# Main.net
KiCad netlist of a schematic drawn in Altium Designer
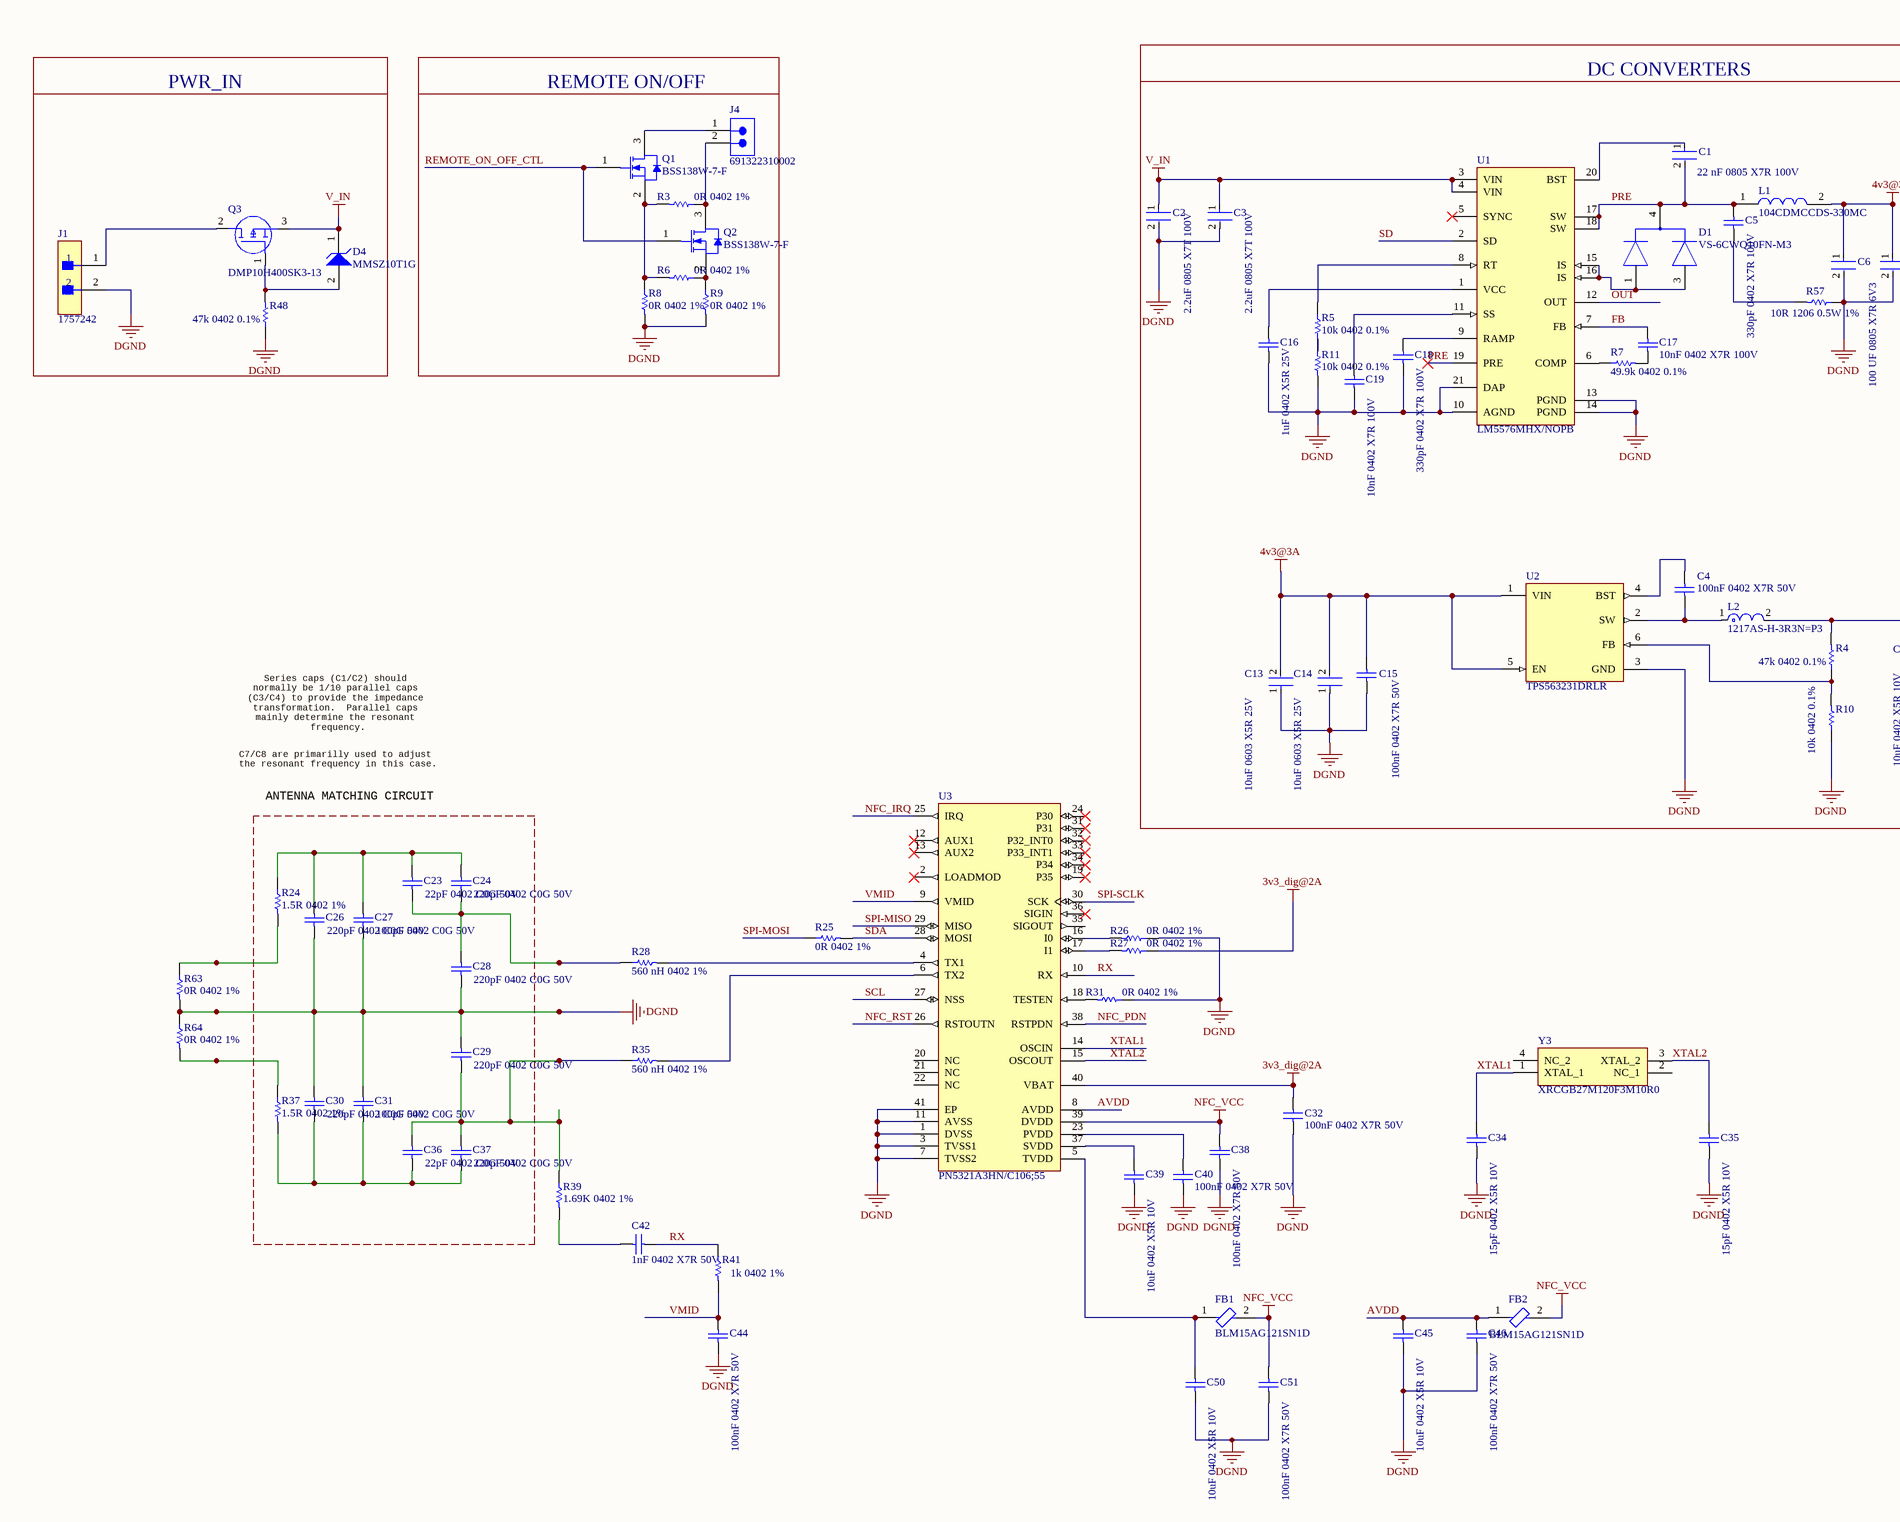
[diagram p0: Main.SchDoc, top left]
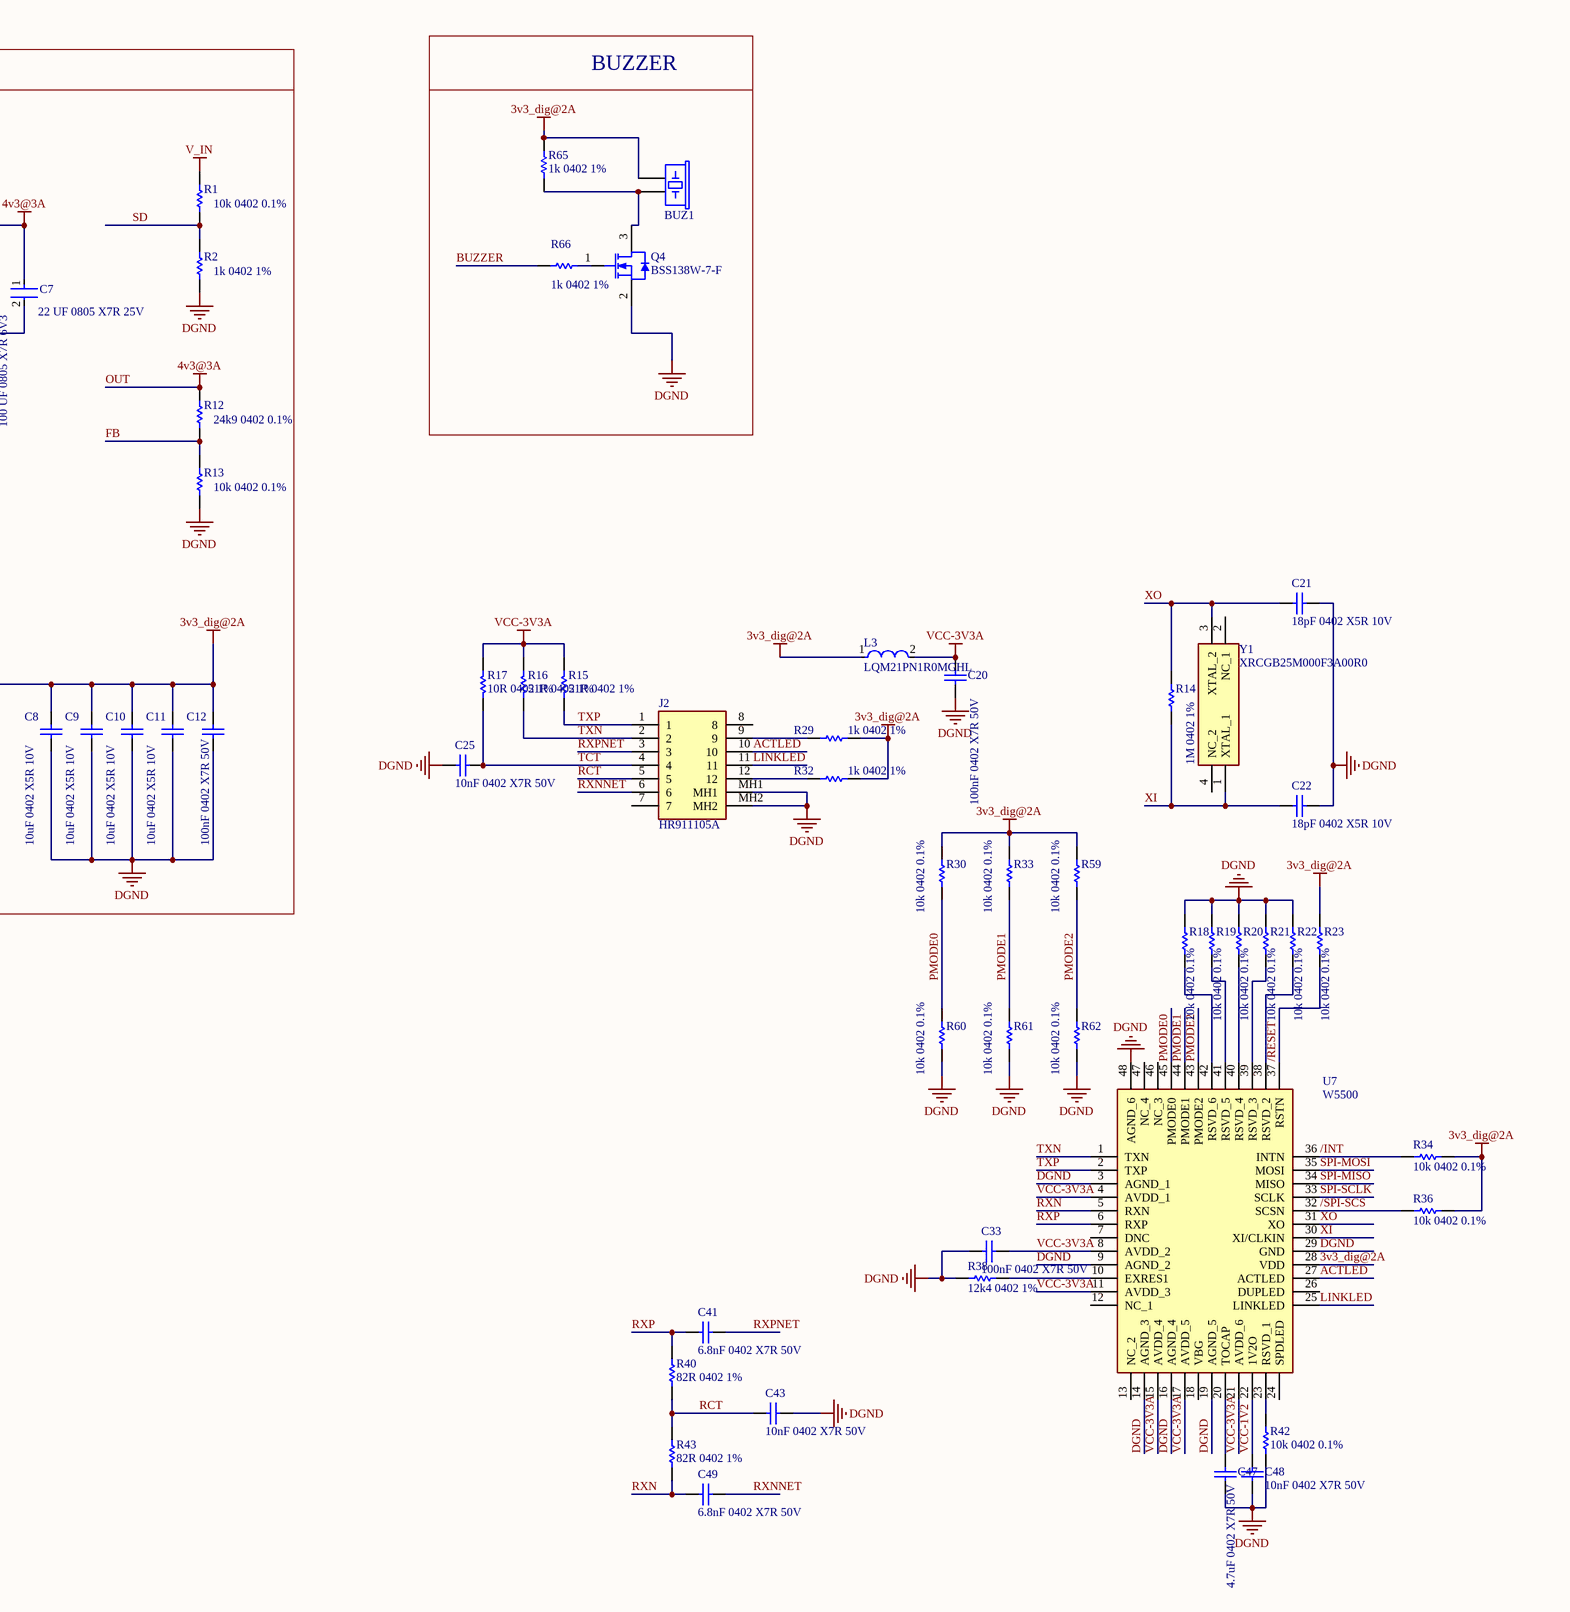
[diagram p1: Main.SchDoc, top right]
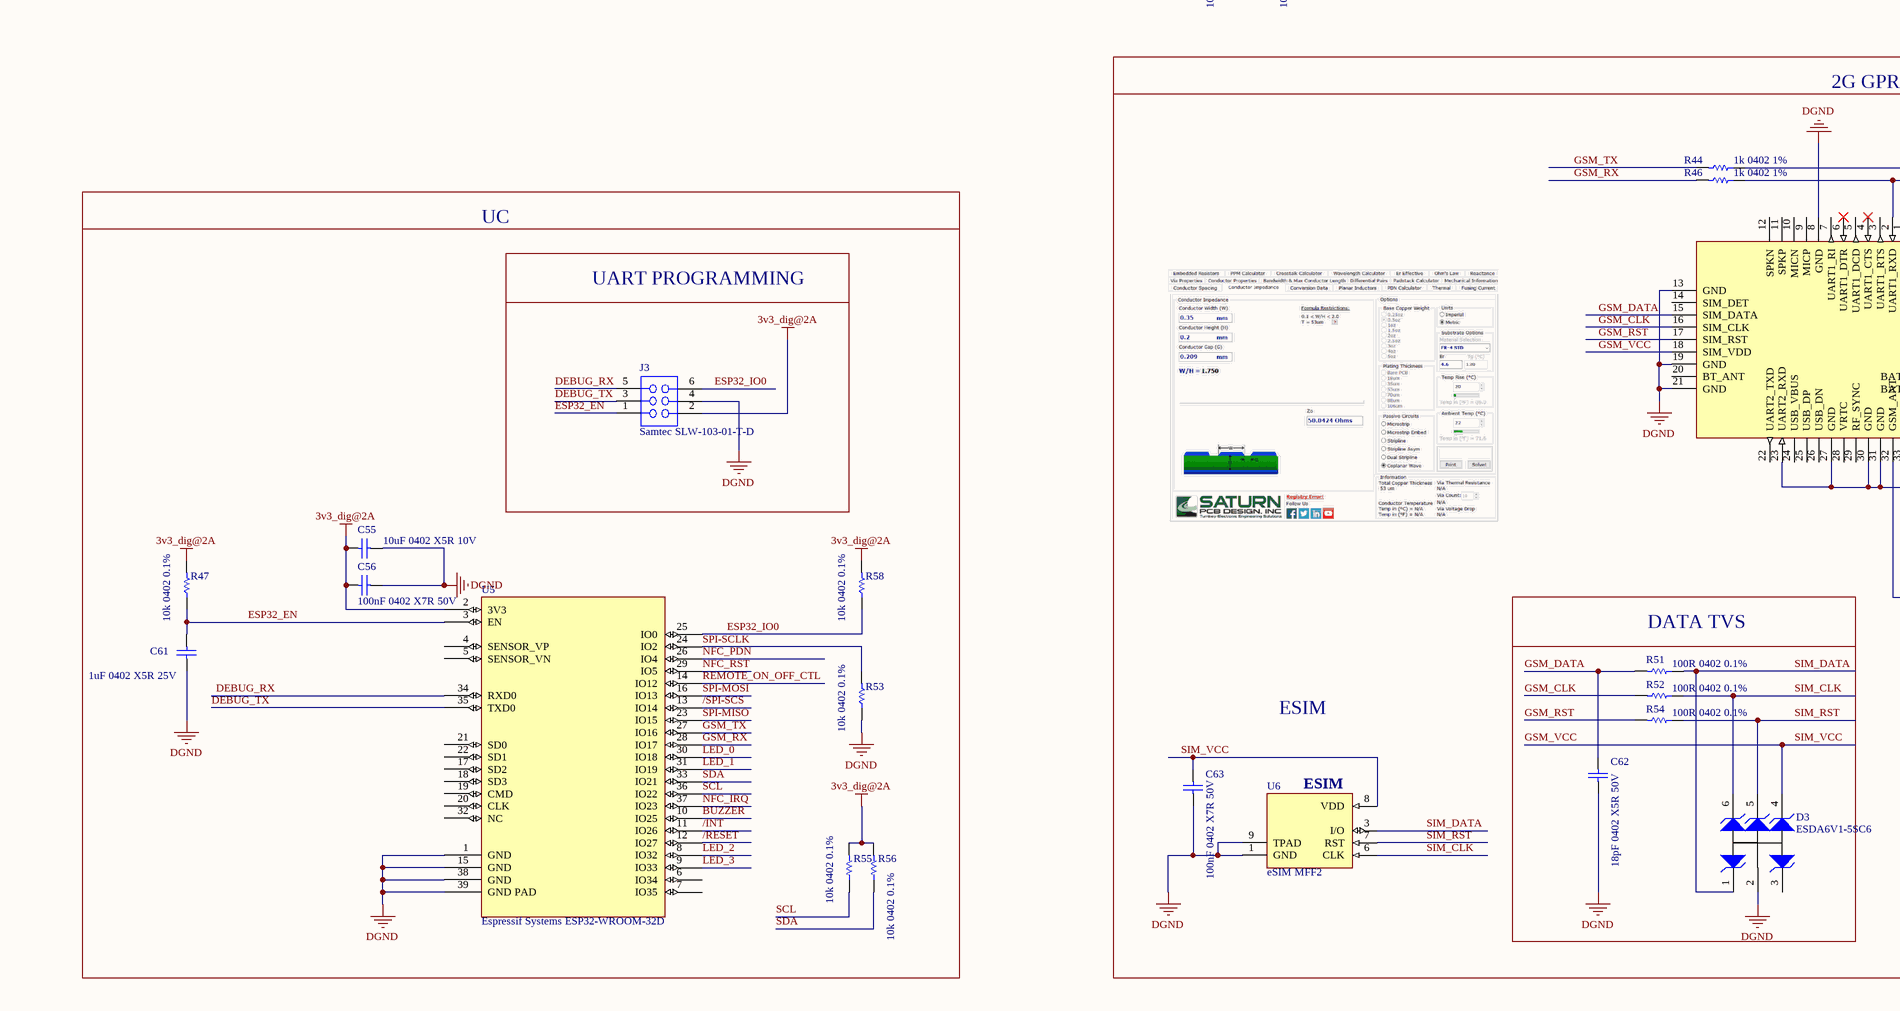
[diagram p2: Main.SchDoc, bottom left]
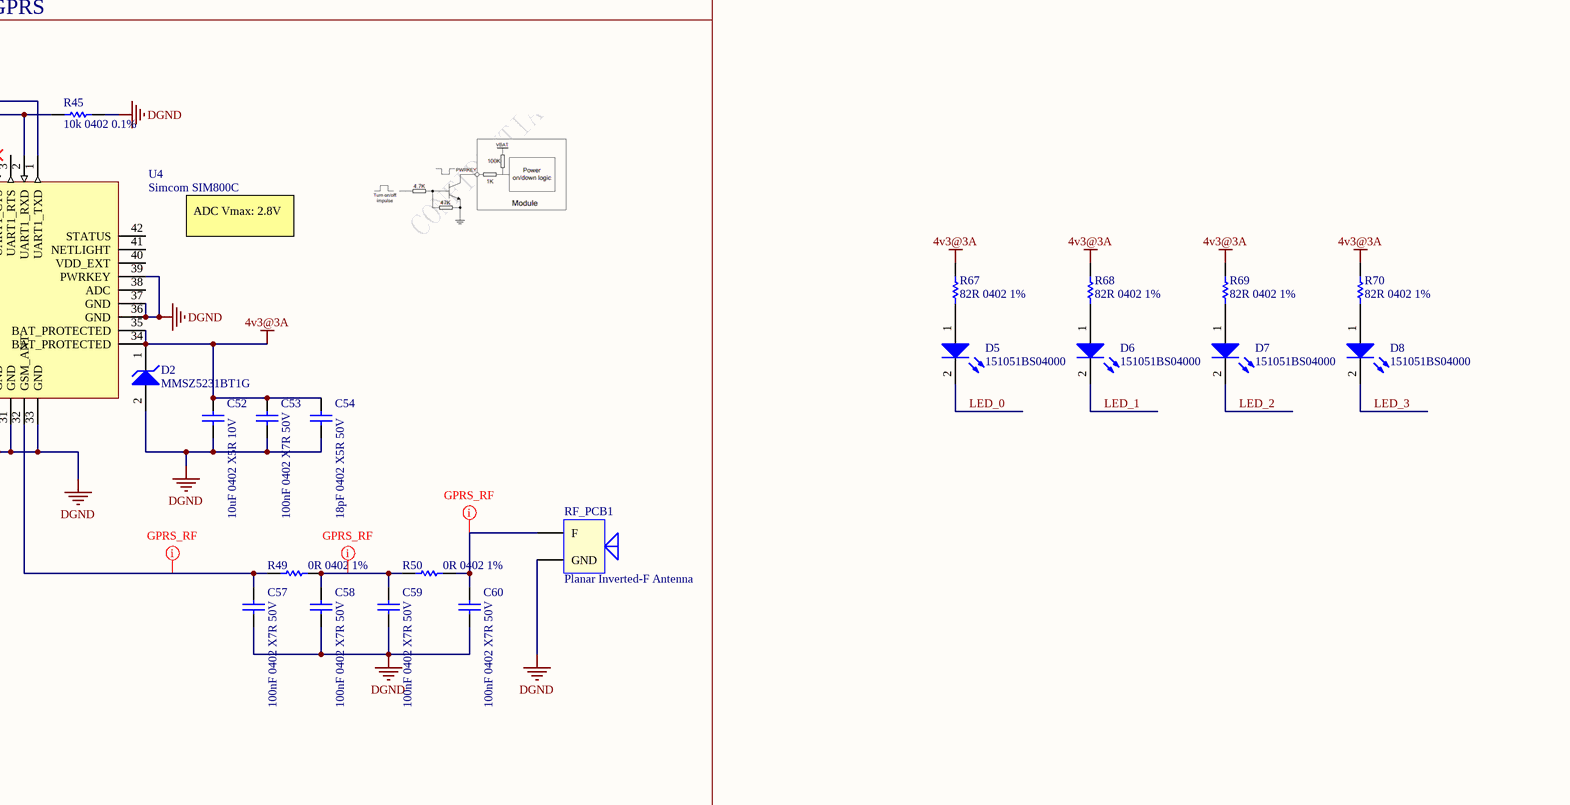
[diagram p3: Main.SchDoc, bottom right]

(export (version "E")
  (design (tool "Eeschema 10.0.6"))
  (components
    (comp (ref "BUZ1")
      (value "CUI CMT-1285C-035")
      (footprint "BUZZER-12MM-NS")
      (description "Audio Buzzer Magnetic 3Vo-p 5Vo-p 70mA 3.5Vo-p 85dB Through Hole Pin Tray")
      (fields (field (name "MANUFACTURER PART NUMBER") "CMT-1285C-035"))
      (libsource (lib "in3ator") (part "CMP-581a9557be5887dd-1"))
    )
    (comp (ref "C1")
      (value "22 nF 0805 X7R 100V")
      (footprint "FP-GRM21B-0_15-IPC_C")
      (fields (field (name "VOLTAGE") "25V") (field (name "TOLERANCE") "10%"))
      (libsource (lib "Altium Content Vault") (part "b4654b650e69147ec39a6b967a45e02"))
    )
    (comp (ref "C2")
      (value "2.2uF 0805 X7T 100V")
      (footprint "FP-GRM21B-0_15-IPC_C")
      (description "Chip Multilayer Ceramic Capacitors for General Purpose, 0805, 2.2uF, X7T, 15%, 10%, 100V")
      (fields (field (name "VOLTAGE") "25V") (field (name "TOLERANCE") "10%"))
      (libsource (lib "Altium Content Vault") (part "b4654b650e69147ec39a6b967a45e02"))
    )
    (comp (ref "C3")
      (value "2.2uF 0805 X7T 100V")
      (footprint "FP-GRM21B-0_15-IPC_C")
      (description "Chip Multilayer Ceramic Capacitors for General Purpose, 0805, 2.2uF, X7T, 15%, 10%, 100V")
      (fields (field (name "VOLTAGE") "25V") (field (name "TOLERANCE") "10%"))
      (libsource (lib "Altium Content Vault") (part "b4654b650e69147ec39a6b967a45e02"))
    )
    (comp (ref "C4")
      (value "100nF 0402 X7R 50V")
      (footprint "CAPC1005X55X25NL5T10")
      (libsource (lib "Altium Content Vault") (part "CAP-NP-2"))
    )
    (comp (ref "C5")
      (value "330pF 0402 X7R 100V")
      (footprint "CAPC1005X55X25NL5T10")
      (libsource (lib "Altium Content Vault") (part "CAP-NP-2"))
    )
    (comp (ref "C6")
      (value "100 UF 0805 X7R 6V3")
      (footprint "FP-GRM21B-0_15-IPC_C")
      (fields (field (name "VOLTAGE") "25V") (field (name "TOLERANCE") "10%"))
      (libsource (lib "Altium Content Vault") (part "b4654b650e69147ec39a6b967a45e02"))
    )
    (comp (ref "C7")
      (value "22 UF 0805 X7R 25V")
      (footprint "FP-GRM21B-0_15-IPC_C")
      (fields (field (name "VOLTAGE") "25V") (field (name "TOLERANCE") "10%"))
      (libsource (lib "Altium Content Vault") (part "b4654b650e69147ec39a6b967a45e02"))
    )
    (comp (ref "C8")
      (value "10uF 0402 X5R 10V")
      (footprint "CAPC1005X55X25NL5T10")
      (libsource (lib "Altium Content Vault") (part "CAP-NP-2"))
    )
    (comp (ref "C9")
      (value "10uF 0402 X5R 10V")
      (footprint "CAPC1005X55X25NL5T10")
      (libsource (lib "Altium Content Vault") (part "CAP-NP-2"))
    )
    (comp (ref "C10")
      (value "10uF 0402 X5R 10V")
      (footprint "CAPC1005X55X25NL5T10")
      (libsource (lib "Altium Content Vault") (part "CAP-NP-2"))
    )
    (comp (ref "C11")
      (value "10uF 0402 X5R 10V")
      (footprint "CAPC1005X55X25NL5T10")
      (libsource (lib "Altium Content Vault") (part "CAP-NP-2"))
    )
    (comp (ref "C12")
      (value "100nF 0402 X7R 50V")
      (footprint "CAPC1005X55X25NL5T10")
      (libsource (lib "Altium Content Vault") (part "CAP-NP-2"))
    )
    (comp (ref "C13")
      (value "10uF 0603 X5R 25V")
      (footprint "FP-GRM188-0_2-IPC_B")
      (libsource (lib "Altium Content Vault") (part "11868f565c42a9108669ba33697ecf6"))
    )
    (comp (ref "C14")
      (value "10uF 0603 X5R 25V")
      (footprint "FP-GRM188-0_2-IPC_B")
      (libsource (lib "Altium Content Vault") (part "11868f565c42a9108669ba33697ecf6"))
    )
    (comp (ref "C15")
      (value "100nF 0402 X7R 50V")
      (footprint "CAPC1005X55X25NL5T10")
      (libsource (lib "Altium Content Vault") (part "CAP-NP-2"))
    )
    (comp (ref "C16")
      (value "1uF 0402 X5R 25V")
      (footprint "CAPC1005X55X25NL5T10")
      (libsource (lib "Altium Content Vault") (part "CAP-NP-2"))
    )
    (comp (ref "C17")
      (value "10nF 0402 X7R 100V")
      (footprint "CAPC1005X55X25NL5T10")
      (libsource (lib "Altium Content Vault") (part "CAP-NP-2"))
    )
    (comp (ref "C18")
      (value "330pF 0402 X7R 100V")
      (footprint "CAPC1005X55X25NL5T10")
      (libsource (lib "Altium Content Vault") (part "CAP-NP-2"))
    )
    (comp (ref "C19")
      (value "10nF 0402 X7R 100V")
      (footprint "CAPC1005X55X25NL5T10")
      (libsource (lib "Altium Content Vault") (part "CAP-NP-2"))
    )
    (comp (ref "C20")
      (value "100nF 0402 X7R 50V")
      (footprint "CAPC1005X55X25NL5T10")
      (libsource (lib "Altium Content Vault") (part "CAP-NP-2"))
    )
    (comp (ref "C21")
      (value "18pF 0402 X5R 10V")
      (footprint "CAPC1005X55X25NL5T10")
      (libsource (lib "Altium Content Vault") (part "CAP-NP-2"))
    )
    (comp (ref "C22")
      (value "18pF 0402 X5R 10V")
      (footprint "CAPC1005X55X25NL5T10")
      (libsource (lib "Altium Content Vault") (part "CAP-NP-2"))
    )
    (comp (ref "C23")
      (value "22pF 0402 C0G 50V")
      (footprint "CAPC1005X55X25NL5T10")
      (libsource (lib "Altium Content Vault") (part "CAP-NP-2"))
    )
    (comp (ref "C24")
      (value "220pF 0402 C0G 50V")
      (footprint "CAPC1005X55X25NL5T10")
      (libsource (lib "Altium Content Vault") (part "CAP-NP-2"))
    )
    (comp (ref "C25")
      (value "10nF 0402 X7R 50V")
      (footprint "CAPC1005X55X25NL5T10")
      (libsource (lib "Altium Content Vault") (part "CAP-NP-2"))
    )
    (comp (ref "C26")
      (value "220pF 0402 C0G 50V")
      (footprint "CAPC1005X55X25NL5T10")
      (libsource (lib "Altium Content Vault") (part "CAP-NP-2"))
    )
    (comp (ref "C27")
      (value "100pF 0402 C0G 50V")
      (footprint "CAPC1005X55X25NL5T10")
      (libsource (lib "Altium Content Vault") (part "CAP-NP-2"))
    )
    (comp (ref "C28")
      (value "220pF 0402 C0G 50V")
      (footprint "CAPC1005X55X25NL5T10")
      (libsource (lib "Altium Content Vault") (part "CAP-NP-2"))
    )
    (comp (ref "C29")
      (value "220pF 0402 C0G 50V")
      (footprint "CAPC1005X55X25NL5T10")
      (libsource (lib "Altium Content Vault") (part "CAP-NP-2"))
    )
    (comp (ref "C30")
      (value "220pF 0402 C0G 50V")
      (footprint "CAPC1005X55X25NL5T10")
      (libsource (lib "Altium Content Vault") (part "CAP-NP-2"))
    )
    (comp (ref "C31")
      (value "100pF 0402 C0G 50V")
      (footprint "CAPC1005X55X25NL5T10")
      (libsource (lib "Altium Content Vault") (part "CAP-NP-2"))
    )
    (comp (ref "C32")
      (value "100nF 0402 X7R 50V")
      (footprint "CAPC1005X55X25NL5T10")
      (libsource (lib "Altium Content Vault") (part "CAP-NP-2"))
    )
    (comp (ref "C33")
      (value "100nF 0402 X7R 50V")
      (footprint "CAPC1005X55X25NL5T10")
      (libsource (lib "Altium Content Vault") (part "CAP-NP-2"))
    )
    (comp (ref "C34")
      (value "15pF 0402 X5R 10V")
      (footprint "CAPC1005X55X25NL5T10")
      (libsource (lib "Altium Content Vault") (part "CAP-NP-2"))
    )
    (comp (ref "C35")
      (value "15pF 0402 X5R 10V")
      (footprint "CAPC1005X55X25NL5T10")
      (libsource (lib "Altium Content Vault") (part "CAP-NP-2"))
    )
    (comp (ref "C36")
      (value "22pF 0402 C0G 50V")
      (footprint "CAPC1005X55X25NL5T10")
      (libsource (lib "Altium Content Vault") (part "CAP-NP-2"))
    )
    (comp (ref "C37")
      (value "220pF 0402 C0G 50V")
      (footprint "CAPC1005X55X25NL5T10")
      (libsource (lib "Altium Content Vault") (part "CAP-NP-2"))
    )
    (comp (ref "C38")
      (value "100nF 0402 X7R 50V")
      (footprint "CAPC1005X55X25NL5T10")
      (libsource (lib "Altium Content Vault") (part "CAP-NP-2"))
    )
    (comp (ref "C39")
      (value "10uF 0402 X5R 10V")
      (footprint "CAPC1005X55X25NL5T10")
      (libsource (lib "Altium Content Vault") (part "CAP-NP-2"))
    )
    (comp (ref "C40")
      (value "100nF 0402 X7R 50V")
      (footprint "CAPC1005X55X25NL5T10")
      (libsource (lib "Altium Content Vault") (part "CAP-NP-2"))
    )
    (comp (ref "C41")
      (value "6.8nF 0402 X7R 50V")
      (footprint "CAPC1005X55X25NL5T10")
      (libsource (lib "Altium Content Vault") (part "CAP-NP-2"))
    )
    (comp (ref "C42")
      (value "1nF 0402 X7R 50V")
      (footprint "CAPC1005X55X25NL5T10")
      (libsource (lib "Altium Content Vault") (part "CAP-NP-2"))
    )
    (comp (ref "C43")
      (value "10nF 0402 X7R 50V")
      (footprint "CAPC1005X55X25NL5T10")
      (libsource (lib "Altium Content Vault") (part "CAP-NP-2"))
    )
    (comp (ref "C44")
      (value "100nF 0402 X7R 50V")
      (footprint "CAPC1005X55X25NL5T10")
      (libsource (lib "Altium Content Vault") (part "CAP-NP-2"))
    )
    (comp (ref "C45")
      (value "10uF 0402 X5R 10V")
      (footprint "CAPC1005X55X25NL5T10")
      (libsource (lib "Altium Content Vault") (part "CAP-NP-2"))
    )
    (comp (ref "C46")
      (value "100nF 0402 X7R 50V")
      (footprint "CAPC1005X55X25NL5T10")
      (libsource (lib "Altium Content Vault") (part "CAP-NP-2"))
    )
    (comp (ref "C47")
      (value "4.7uF 0402 X7R 50V")
      (footprint "CAPC1005X55X25NL5T10")
      (libsource (lib "Altium Content Vault") (part "CAP-NP-2"))
    )
    (comp (ref "C48")
      (value "10nF 0402 X7R 50V")
      (footprint "CAPC1005X55X25NL5T10")
      (libsource (lib "Altium Content Vault") (part "CAP-NP-2"))
    )
    (comp (ref "C49")
      (value "6.8nF 0402 X7R 50V")
      (footprint "CAPC1005X55X25NL5T10")
      (libsource (lib "Altium Content Vault") (part "CAP-NP-2"))
    )
    (comp (ref "C50")
      (value "10uF 0402 X5R 10V")
      (footprint "CAPC1005X55X25NL5T10")
      (libsource (lib "Altium Content Vault") (part "CAP-NP-2"))
    )
    (comp (ref "C51")
      (value "100nF 0402 X7R 50V")
      (footprint "CAPC1005X55X25NL5T10")
      (libsource (lib "Altium Content Vault") (part "CAP-NP-2"))
    )
    (comp (ref "C52")
      (value "10uF 0402 X5R 10V")
      (footprint "CAPC1005X55X25NL5T10")
      (libsource (lib "Altium Content Vault") (part "CAP-NP-2"))
    )
    (comp (ref "C53")
      (value "100nF 0402 X7R 50V")
      (footprint "CAPC1005X55X25NL5T10")
      (libsource (lib "Altium Content Vault") (part "CAP-NP-2"))
    )
    (comp (ref "C54")
      (value "18pF 0402 X5R 50V")
      (footprint "CAPC1005X55X25NL5T10")
      (libsource (lib "Altium Content Vault") (part "CAP-NP-2"))
    )
    (comp (ref "C55")
      (value "10uF 0402 X5R 10V")
      (footprint "CAPC1005X55X25NL5T10")
      (libsource (lib "Altium Content Vault") (part "CAP-NP-2"))
    )
    (comp (ref "C56")
      (value "100nF 0402 X7R 50V")
      (footprint "CAPC1005X55X25NL5T10")
      (libsource (lib "Altium Content Vault") (part "CAP-NP-2"))
    )
    (comp (ref "C57")
      (value "100nF 0402 X7R 50V")
      (footprint "CAPC1005X55X25NL5T10")
      (libsource (lib "Altium Content Vault") (part "CAP-NP-2"))
    )
    (comp (ref "C58")
      (value "100nF 0402 X7R 50V")
      (footprint "CAPC1005X55X25NL5T10")
      (libsource (lib "Altium Content Vault") (part "CAP-NP-2"))
    )
    (comp (ref "C59")
      (value "100nF 0402 X7R 50V")
      (footprint "CAPC1005X55X25NL5T10")
      (libsource (lib "Altium Content Vault") (part "CAP-NP-2"))
    )
    (comp (ref "C60")
      (value "100nF 0402 X7R 50V")
      (footprint "CAPC1005X55X25NL5T10")
      (libsource (lib "Altium Content Vault") (part "CAP-NP-2"))
    )
    (comp (ref "C61")
      (value "1uF 0402 X5R 25V")
      (footprint "CAPC1005X55X25NL5T10")
      (libsource (lib "Altium Content Vault") (part "CAP-NP-2"))
    )
    (comp (ref "C62")
      (value "18pF 0402 X5R 50V")
      (footprint "CAPC1005X55X25NL5T10")
      (libsource (lib "Altium Content Vault") (part "CAP-NP-2"))
    )
    (comp (ref "C63")
      (value "100nF 0402 X7R 50V")
      (footprint "CAPC1005X55X25NL5T10")
      (libsource (lib "Altium Content Vault") (part "CAP-NP-2"))
    )
    (comp (ref "D1")
      (value "VS-6CWQ10FN-M3")
      (footprint "FP-95627-0")
      (description "VS-6CWQ10FN-M3 Rectifier Diode, Schottky, 1 Phase, 2 Element, 7A, 100V V(RRM), Silicon, TO-252AA")
      (libsource (lib "Altium Content Vault") (part "8cea5ace56f6096956c40e30c0f019d"))
    )
    (comp (ref "D2")
      (value "MMSZ5231BT1G")
      (footprint "ONSC-SOD-123-2-425-04_V")
      (description "Zener Voltage Regulator, 500 mW, 2-Pin SOD-123, Pb-Free, Tape and Reel")
      (fields (field (name "MANUFACTURER") "On Semiconductor"))
      (libsource (lib "Altium Content Vault") (part "ONSC-K1A2-2"))
    )
    (comp (ref "D3")
      (value "ESDA6V1-5SC6")
      (footprint "MF06A_N")
      (description "ESDA Series 5 Channel 6.1 V 50 pF SMT Uni Directional Transil Array - SOT-23-6L")
      (libsource (lib "in3ator_components") (part "CMP-924f5b40f9684d88-1"))
    )
    (comp (ref "D4")
      (value "MMSZ10T1G")
      (footprint "ONSC-SOD-123-2-425-04_V")
      (description "Zener Voltage Regulator, 500 mW, 2-Pin SOD-123, Pb-Free, Tape and Reel")
      (fields (field (name "MANUFACTURER") "On Semiconductor"))
      (libsource (lib "Altium Content Vault") (part "ONSC-K1A2-2"))
    )
    (comp (ref "D5")
      (value "151051BS04000")
      (footprint "WL-TMRC_D5.9H8.7")
      (libsource (lib "Altium Content Vault") (part "LED_Blue_1A-2K"))
    )
    (comp (ref "D6")
      (value "151051BS04000")
      (footprint "WL-TMRC_D5.9H8.7")
      (libsource (lib "Altium Content Vault") (part "LED_Blue_1A-2K"))
    )
    (comp (ref "D7")
      (value "151051BS04000")
      (footprint "WL-TMRC_D5.9H8.7")
      (libsource (lib "Altium Content Vault") (part "LED_Blue_1A-2K"))
    )
    (comp (ref "D8")
      (value "151051BS04000")
      (footprint "WL-TMRC_D5.9H8.7")
      (libsource (lib "Altium Content Vault") (part "LED_Blue_1A-2K"))
    )
    (comp (ref "FB1")
      (value "BLM15AG121SN1D")
      (footprint "FP-BLM15-0_05-MFG")
      (description "Chip Ferrite Bead, 0402, 120Ω @ 100MHz, 0.19Ω, 25%, 550mA")
      (fields (field (name "TOLERANCE") "25%"))
      (libsource (lib "Altium Content Vault") (part "5f30dd21d616792df468990f7003faa"))
    )
    (comp (ref "FB2")
      (value "BLM15AG121SN1D")
      (footprint "FP-BLM15-0_05-MFG")
      (description "Chip Ferrite Bead, 0402, 120Ω @ 100MHz, 0.19Ω, 25%, 550mA")
      (fields (field (name "TOLERANCE") "25%"))
      (libsource (lib "Altium Content Vault") (part "5f30dd21d616792df468990f7003faa"))
    )
    (comp (ref "J1")
      (value "1757242")
      (footprint "FP-1757242-MFG")
      (description "TERM BLOCK HDR 2POS 90DEG 5.08MM")
      (fields (field (name "VOLTAGE") "300V"))
      (libsource (lib "Altium Content Vault") (part "3bc925449376181038e59eaffc5286c"))
    )
    (comp (ref "J2")
      (value "HR911105A")
      (footprint "SamacSys:HR911105A")
      (description "Connector")
      (libsource (lib "*") (part "HR911105A"))
    )
    (comp (ref "J3")
      (value "Samtec SLW-103-01-T-D")
      (footprint "PCB-37z8hw1ej4f71bosen9e-1")
      (description "Dual Row Connector Female Samtec SLW-103-01-T-D")
      (fields (field (name "MANUFACTURER PART NUMBER") "SLW-103-01-T-D"))
      (libsource (lib "in3ator") (part "CMP-bcf575fbeff46332-1"))
    )
    (comp (ref "J4")
      (value "691322310002")
      (footprint "691322310002")
      (fields (field (name "VOLTAGE") "300V"))
      (libsource (lib "Altium Content Vault") (part "TBL - 1R - 02P - Male"))
    )
    (comp (ref "L1")
      (value "104CDMCCDS-330MC")
      (footprint "SamacSys:INDPM115100X400N")
      (description "Inductor")
      (fields (field (name "MOUSER PART NUMBER") "851-104CDMCCDS-330MC"))
      (libsource (lib "*") (part "104CDMCCDS-330MC"))
    )
    (comp (ref "L2")
      (value "1217AS-H-3R3N=P3")
      (footprint "FP-DEM8045C-MFG")
      (description "Shielded Wirewound Inductor 3.3uH 30% 6800mA 0.0144Ω SMD")
      (fields (field (name "TOLERANCE") "30%"))
      (libsource (lib "Altium Content Vault") (part "4cc4b267dca4c8e51f7102f422741d8"))
    )
    (comp (ref "L3")
      (value "LQM21PN1R0MGHL")
      (footprint "FP-LQM21PH_G0-MFG")
      (description "Multilayer Type Inductor for Power Lines, 0805 (2012), 1μH, 20%, 0.1Ω, 2A")
      (fields (field (name "TOLERANCE") "20%"))
      (libsource (lib "Altium Content Vault") (part "725321dda6339637d4d059423bc1c3c"))
    )
    (comp (ref "Q1")
      (value "BSS138W-7-F")
      (footprint "DIOD-SOT323-3_V")
      (fields (field (name "MANUFACTURER") "DiodesIncorporated"))
      (libsource (lib "Altium Content Vault") (part "NEMOS-GSD-3"))
    )
    (comp (ref "Q2")
      (value "BSS138W-7-F")
      (footprint "DIOD-SOT323-3_V")
      (fields (field (name "MANUFACTURER") "DiodesIncorporated"))
      (libsource (lib "Altium Content Vault") (part "NEMOS-GSD-3"))
    )
    (comp (ref "Q3")
      (value "DMP10H400SK3-13")
      (footprint "SamacSys:DMP10H400SK313")
      (description "MOSFET (P-Channel)")
      (fields (field (name "MOUSER PART NUMBER") "621-DMP10H400SK3-13"))
      (libsource (lib "*") (part "DMP10H400SK3-13"))
    )
    (comp (ref "Q4")
      (value "BSS138W-7-F")
      (footprint "DIOD-SOT323-3_V")
      (fields (field (name "MANUFACTURER") "DiodesIncorporated"))
      (libsource (lib "Altium Content Vault") (part "NEMOS-GSD-3"))
    )
    (comp (ref "R1")
      (value "10k 0402 0.1%")
      (footprint "RESC1005X40X25ML05T10")
      (libsource (lib "Altium Content Vault") (part "RES"))
    )
    (comp (ref "R2")
      (value "1k 0402 1%")
      (footprint "RESC1005X40X25ML05T10")
      (libsource (lib "Altium Content Vault") (part "RES"))
    )
    (comp (ref "R3")
      (value "0R 0402 1%")
      (footprint "RESC1005X40X25ML05T10")
      (libsource (lib "Altium Content Vault") (part "RES"))
    )
    (comp (ref "R4")
      (value "47k 0402 0.1%")
      (footprint "RESC1005X40X25ML05T10")
      (libsource (lib "Altium Content Vault") (part "RES"))
    )
    (comp (ref "R5")
      (value "10k 0402 0.1%")
      (footprint "RESC1005X40X25ML05T10")
      (libsource (lib "Altium Content Vault") (part "RES"))
    )
    (comp (ref "R6")
      (value "0R 0402 1%")
      (footprint "RESC1005X40X25ML05T10")
      (libsource (lib "Altium Content Vault") (part "RES"))
    )
    (comp (ref "R7")
      (value "49.9k 0402 0.1%")
      (footprint "RESC1005X40X25ML05T10")
      (libsource (lib "Altium Content Vault") (part "RES"))
    )
    (comp (ref "R8")
      (value "0R 0402 1%")
      (footprint "RESC1005X40X25ML05T10")
      (libsource (lib "Altium Content Vault") (part "RES"))
    )
    (comp (ref "R9")
      (value "0R 0402 1%")
      (footprint "RESC1005X40X25ML05T10")
      (libsource (lib "Altium Content Vault") (part "RES"))
    )
    (comp (ref "R10")
      (value "10k 0402 0.1%")
      (footprint "RESC1005X40X25ML05T10")
      (libsource (lib "Altium Content Vault") (part "RES"))
    )
    (comp (ref "R11")
      (value "10k 0402 0.1%")
      (footprint "RESC1005X40X25ML05T10")
      (libsource (lib "Altium Content Vault") (part "RES"))
    )
    (comp (ref "R12")
      (value "24k9 0402 0.1%")
      (footprint "RESC1005X40X25ML05T10")
      (libsource (lib "Altium Content Vault") (part "RES"))
    )
    (comp (ref "R13")
      (value "10k 0402 0.1%")
      (footprint "RESC1005X40X25ML05T10")
      (libsource (lib "Altium Content Vault") (part "RES"))
    )
    (comp (ref "R14")
      (value "1M 0402 1%")
      (footprint "RESC1005X40X25ML05T10")
      (libsource (lib "Altium Content Vault") (part "RES"))
    )
    (comp (ref "R15")
      (value "51R 0402 1%")
      (footprint "RESC1005X40X25ML05T10")
      (libsource (lib "Altium Content Vault") (part "RES"))
    )
    (comp (ref "R16")
      (value "51R 0402 1%")
      (footprint "RESC1005X40X25ML05T10")
      (libsource (lib "Altium Content Vault") (part "RES"))
    )
    (comp (ref "R17")
      (value "10R 0402 1%")
      (footprint "RESC1005X40X25ML05T10")
      (libsource (lib "Altium Content Vault") (part "RES"))
    )
    (comp (ref "R18")
      (value "10k 0402 0.1%")
      (footprint "RESC1005X40X25ML05T10")
      (libsource (lib "Altium Content Vault") (part "RES"))
    )
    (comp (ref "R19")
      (value "10k 0402 0.1%")
      (footprint "RESC1005X40X25ML05T10")
      (libsource (lib "Altium Content Vault") (part "RES"))
    )
    (comp (ref "R20")
      (value "10k 0402 0.1%")
      (footprint "RESC1005X40X25ML05T10")
      (libsource (lib "Altium Content Vault") (part "RES"))
    )
    (comp (ref "R21")
      (value "10k 0402 0.1%")
      (footprint "RESC1005X40X25ML05T10")
      (libsource (lib "Altium Content Vault") (part "RES"))
    )
    (comp (ref "R22")
      (value "10k 0402 0.1%")
      (footprint "RESC1005X40X25ML05T10")
      (libsource (lib "Altium Content Vault") (part "RES"))
    )
    (comp (ref "R23")
      (value "10k 0402 0.1%")
      (footprint "RESC1005X40X25ML05T10")
      (libsource (lib "Altium Content Vault") (part "RES"))
    )
    (comp (ref "R24")
      (value "1.5R 0402 1%")
      (footprint "RESC1005X40X25ML05T10")
      (libsource (lib "Altium Content Vault") (part "RES"))
    )
    (comp (ref "R25")
      (value "0R 0402 1%")
      (footprint "RESC1005X40X25ML05T10")
      (libsource (lib "Altium Content Vault") (part "RES"))
    )
    (comp (ref "R26")
      (value "0R 0402 1%")
      (footprint "RESC1005X40X25ML05T10")
      (libsource (lib "Altium Content Vault") (part "RES"))
    )
    (comp (ref "R27")
      (value "0R 0402 1%")
      (footprint "RESC1005X40X25ML05T10")
      (libsource (lib "Altium Content Vault") (part "RES"))
    )
    (comp (ref "R28")
      (value "560 nH 0402 1%")
      (footprint "RESC1005X40X25ML05T10")
      (libsource (lib "Altium Content Vault") (part "RES"))
    )
    (comp (ref "R29")
      (value "1k 0402 1%")
      (footprint "RESC1005X40X25ML05T10")
      (libsource (lib "Altium Content Vault") (part "RES"))
    )
    (comp (ref "R30")
      (value "10k 0402 0.1%")
      (footprint "RESC1005X40X25ML05T10")
      (libsource (lib "Altium Content Vault") (part "RES"))
    )
    (comp (ref "R31")
      (value "0R 0402 1%")
      (footprint "RESC1005X40X25ML05T10")
      (libsource (lib "Altium Content Vault") (part "RES"))
    )
    (comp (ref "R32")
      (value "1k 0402 1%")
      (footprint "RESC1005X40X25ML05T10")
      (libsource (lib "Altium Content Vault") (part "RES"))
    )
    (comp (ref "R33")
      (value "10k 0402 0.1%")
      (footprint "RESC1005X40X25ML05T10")
      (libsource (lib "Altium Content Vault") (part "RES"))
    )
    (comp (ref "R34")
      (value "10k 0402 0.1%")
      (footprint "RESC1005X40X25ML05T10")
      (libsource (lib "Altium Content Vault") (part "RES"))
    )
    (comp (ref "R35")
      (value "560 nH 0402 1%")
      (footprint "RESC1005X40X25ML05T10")
      (libsource (lib "Altium Content Vault") (part "RES"))
    )
    (comp (ref "R36")
      (value "10k 0402 0.1%")
      (footprint "RESC1005X40X25ML05T10")
      (libsource (lib "Altium Content Vault") (part "RES"))
    )
    (comp (ref "R37")
      (value "1.5R 0402 1%")
      (footprint "RESC1005X40X25ML05T10")
      (libsource (lib "Altium Content Vault") (part "RES"))
    )
    (comp (ref "R38")
      (value "12k4 0402 1%")
      (footprint "RESC1005X40X25ML05T10")
      (libsource (lib "Altium Content Vault") (part "RES"))
    )
    (comp (ref "R39")
      (value "1.69K 0402 1%")
      (footprint "RESC1005X40X25ML05T10")
      (libsource (lib "Altium Content Vault") (part "RES"))
    )
    (comp (ref "R40")
      (value "82R 0402 1%")
      (footprint "RESC1005X40X25ML05T10")
      (libsource (lib "Altium Content Vault") (part "RES"))
    )
    (comp (ref "R41")
      (value "1k 0402 1%")
      (footprint "RESC1005X40X25ML05T10")
      (libsource (lib "Altium Content Vault") (part "RES"))
    )
    (comp (ref "R42")
      (value "10k 0402 0.1%")
      (footprint "RESC1005X40X25ML05T10")
      (libsource (lib "Altium Content Vault") (part "RES"))
    )
    (comp (ref "R43")
      (value "82R 0402 1%")
      (footprint "RESC1005X40X25ML05T10")
      (libsource (lib "Altium Content Vault") (part "RES"))
    )
    (comp (ref "R44")
      (value "1k 0402 1%")
      (footprint "RESC1005X40X25ML05T10")
      (libsource (lib "Altium Content Vault") (part "RES"))
    )
    (comp (ref "R45")
      (value "10k 0402 0.1%")
      (footprint "RESC1005X40X25ML05T10")
      (libsource (lib "Altium Content Vault") (part "RES"))
    )
    (comp (ref "R46")
      (value "1k 0402 1%")
      (footprint "RESC1005X40X25ML05T10")
      (libsource (lib "Altium Content Vault") (part "RES"))
    )
    (comp (ref "R47")
      (value "10k 0402 0.1%")
      (footprint "RESC1005X40X25ML05T10")
      (libsource (lib "Altium Content Vault") (part "RES"))
    )
    (comp (ref "R48")
      (value "47k 0402 0.1%")
      (footprint "RESC1005X40X25ML05T10")
      (libsource (lib "Altium Content Vault") (part "RES"))
    )
    (comp (ref "R49")
      (value "0R 0402 1%")
      (footprint "RESC1005X40X25ML05T10")
      (libsource (lib "Altium Content Vault") (part "RES"))
    )
    (comp (ref "R50")
      (value "0R 0402 1%")
      (footprint "RESC1005X40X25ML05T10")
      (libsource (lib "Altium Content Vault") (part "RES"))
    )
    (comp (ref "R51")
      (value "100R 0402 0.1%")
      (footprint "RESC1005X40X25ML05T10")
      (libsource (lib "Altium Content Vault") (part "RES"))
    )
    (comp (ref "R52")
      (value "100R 0402 0.1%")
      (footprint "RESC1005X40X25ML05T10")
      (libsource (lib "Altium Content Vault") (part "RES"))
    )
    (comp (ref "R53")
      (value "10k 0402 0.1%")
      (footprint "RESC1005X40X25ML05T10")
      (libsource (lib "Altium Content Vault") (part "RES"))
    )
    (comp (ref "R54")
      (value "100R 0402 0.1%")
      (footprint "RESC1005X40X25ML05T10")
      (libsource (lib "Altium Content Vault") (part "RES"))
    )
    (comp (ref "R55")
      (value "10k 0402 0.1%")
      (footprint "RESC1005X40X25ML05T10")
      (libsource (lib "Altium Content Vault") (part "RES"))
    )
    (comp (ref "R56")
      (value "10k 0402 0.1%")
      (footprint "RESC1005X40X25ML05T10")
      (libsource (lib "Altium Content Vault") (part "RES"))
    )
    (comp (ref "R57")
      (value "10R 1206 0.5W 1%")
      (footprint "CAPC3216X180X55ML20T25")
      (fields (field (name "MANUFACTURER PART NUMBER") "WSLP12065L000FEA") (field (name "POWER") "1W"))
      (libsource (lib "in3ator") (part "CMP-0abdc173b10ad57a-1"))
    )
    (comp (ref "R58")
      (value "10k 0402 0.1%")
      (footprint "RESC1005X40X25ML05T10")
      (libsource (lib "Altium Content Vault") (part "RES"))
    )
    (comp (ref "R59")
      (value "10k 0402 0.1%")
      (footprint "RESC1005X40X25ML05T10")
      (libsource (lib "Altium Content Vault") (part "RES"))
    )
    (comp (ref "R60")
      (value "10k 0402 0.1%")
      (footprint "RESC1005X40X25ML05T10")
      (libsource (lib "Altium Content Vault") (part "RES"))
    )
    (comp (ref "R61")
      (value "10k 0402 0.1%")
      (footprint "RESC1005X40X25ML05T10")
      (libsource (lib "Altium Content Vault") (part "RES"))
    )
    (comp (ref "R62")
      (value "10k 0402 0.1%")
      (footprint "RESC1005X40X25ML05T10")
      (libsource (lib "Altium Content Vault") (part "RES"))
    )
    (comp (ref "R63")
      (value "0R 0402 1%")
      (footprint "RESC1005X40X25ML05T10")
      (libsource (lib "Altium Content Vault") (part "RES"))
    )
    (comp (ref "R64")
      (value "0R 0402 1%")
      (footprint "RESC1005X40X25ML05T10")
      (libsource (lib "Altium Content Vault") (part "RES"))
    )
    (comp (ref "R65")
      (value "1k 0402 1%")
      (footprint "RESC1005X40X25ML05T10")
      (libsource (lib "Altium Content Vault") (part "RES"))
    )
    (comp (ref "R66")
      (value "1k 0402 1%")
      (footprint "RESC1005X40X25ML05T10")
      (libsource (lib "Altium Content Vault") (part "RES"))
    )
    (comp (ref "R67")
      (value "82R 0402 1%")
      (footprint "RESC1005X40X25ML05T10")
      (libsource (lib "Altium Content Vault") (part "RES"))
    )
    (comp (ref "R68")
      (value "82R 0402 1%")
      (footprint "RESC1005X40X25ML05T10")
      (libsource (lib "Altium Content Vault") (part "RES"))
    )
    (comp (ref "R69")
      (value "82R 0402 1%")
      (footprint "RESC1005X40X25ML05T10")
      (libsource (lib "Altium Content Vault") (part "RES"))
    )
    (comp (ref "R70")
      (value "82R 0402 1%")
      (footprint "RESC1005X40X25ML05T10")
      (libsource (lib "Altium Content Vault") (part "RES"))
    )
    (comp (ref "RF_PCB1")
      (value "Planar Inverted-F Antenna")
      (footprint "PCB-k9titb4465gfk1ijwrnj-1")
      (description "GSM900 and GSM1800  Frequency Bands PCB antenna")
      (libsource (lib "in3ator") (part "CMP-e704afk8c25r4a5ypw1c-12"))
    )
    (comp (ref "U1")
      (value "LM5576MHX/NOPB")
      (footprint "PWP0020A_M")
      (description "SIMPLE SWITCHER® 75V, 3A Step-Down Switching Regulator, 20-pin TSSOP-EP, Pb-Free")
      (fields (field (name "MANUFACTURER") "Texas Instruments"))
      (libsource (lib "Altium Content Vault") (part "PM-SWREG-LM25576"))
    )
    (comp (ref "U2")
      (value "TPS563231DRLR")
      (footprint "FP-DRL0006A-MFG")
      (description "POWER MANAGEMENT")
      (libsource (lib "Altium Content Vault") (part "4d860df4d3ea23b1aa54a495432cd8a"))
    )
    (comp (ref "U3")
      (value "PN5321A3HN/C106;55")
      (footprint "NXP-HVQFN-40_M")
      (description "NFC Controller, 13.56 MHz, -30 to 85 degC, 40-Pin HVQFN (SOT618-1), RoHS, Tray")
      (fields (field (name "MANUFACTURER") "NXP Semiconductors"))
      (libsource (lib "Altium Content Vault") (part "NXP-PN5321A3HN-HVQFN-40"))
    )
    (comp (ref "U4")
      (value "Simcom SIM800C")
      (footprint "SIM800C")
      (description "Module: GSM/Bluetooth; GPRS; 2G; 1800MHz, 900MHz; 85.6kbps; SMD")
      (fields (field (name "MANUFACTURER PART NUMBER") "SIM800C"))
      (libsource (lib "in3ator") (part "CMP-72dbb8ea0133ad1c-5"))
    )
    (comp (ref "U5")
      (value "Espressif Systems ESP32-WROOM-32D")
      (footprint "PCB-1htnvixwtci0bg563is1-1")
      (description "SMD Module ESP32-WOOM-32D")
      (fields (field (name "MANUFACTURER PART NUMBER") "ESP32-WOOM-32D"))
      (libsource (lib "in3ator") (part "CMP-2785eb2e468cf842-1"))
    )
    (comp (ref "U6")
      (value "eSIM MFF2")
      (footprint "SON127P600X95_HS-9N")
      (description "Embedded SIM card in MFF2")
      (libsource (lib "in3ator") (part "CMP-ce8f06c57f401148-2"))
    )
    (comp (ref "U7")
      (value "W5500")
      (footprint "SamacSys:QFP50P900X900X160-48N")
      (description "Integrated Circuit")
      (fields (field (name "MOUSER PART NUMBER") "950-W5500"))
      (libsource (lib "SamacSys") (part "W5500"))
    )
    (comp (ref "Y1")
      (value "XRCGB25M000F3A00R0")
      (footprint "SamacSys:XRCGB")
      (description "Crystal or Oscillator")
      (fields (field (name "MOUSER PART NUMBER") "81-XRCGB25M000F3A0R0"))
      (libsource (lib "*") (part "XRCGB25M000F3A00R0"))
    )
    (comp (ref "Y3")
      (value "XRCGB27M120F3M10R0")
      (footprint "SamacSys:XRCGB")
      (description "Crystal or Oscillator")
      (fields (field (name "MOUSER PART NUMBER") "81-XRCGB27M120F3M1R0"))
      (libsource (lib "*") (part "XRCGB27M120F3M10R0"))
    )
  )
  (nets
    (net (code "1") (name "/ACTLED") (class "Default")
      (node (ref "J2") (pin "10") (pinfunction "10_10") (pintype "passive"))
      (node (ref "U7") (pin "27") (pinfunction "ACTLED_27") (pintype "passive"))
    )
    (net (code "2") (name "/AVDD") (class "Default")
      (node (ref "C45") (pin "1") (pinfunction "1_1") (pintype "passive"))
      (node (ref "C46") (pin "1") (pinfunction "1_1") (pintype "passive"))
      (node (ref "FB2") (pin "1") (pinfunction "1_1") (pintype "passive"))
      (node (ref "U3") (pin "8") (pinfunction "AVDD_8") (pintype "power_in"))
    )
    (net (code "3") (name "/BUZZER") (class "Default")
      (node (ref "R66") (pin "2") (pinfunction "2_2") (pintype "passive"))
      (node (ref "U5") (pin "10") (pinfunction "IO25_10") (pintype "bidirectional"))
    )
    (net (code "4") (name "/DEBUG_RX") (class "Default")
      (node (ref "J3") (pin "5") (pinfunction "5_5") (pintype "passive"))
      (node (ref "U5") (pin "34") (pinfunction "RXD0_34") (pintype "bidirectional"))
    )
    (net (code "5") (name "/DEBUG_TX") (class "Default")
      (node (ref "J3") (pin "3") (pinfunction "3_3") (pintype "passive"))
      (node (ref "U5") (pin "35") (pinfunction "TXD0_35") (pintype "bidirectional"))
    )
    (net (code "6") (name "/ESP32_EN") (class "Default")
      (node (ref "C61") (pin "2") (pinfunction "2_2") (pintype "passive"))
      (node (ref "J3") (pin "1") (pinfunction "1_1") (pintype "passive"))
      (node (ref "R47") (pin "1") (pinfunction "1_1") (pintype "passive"))
      (node (ref "U5") (pin "3") (pinfunction "EN_3") (pintype "bidirectional"))
    )
    (net (code "7") (name "/ESP32_IO0") (class "Default")
      (node (ref "J3") (pin "6") (pinfunction "6_6") (pintype "passive"))
      (node (ref "R58") (pin "1") (pinfunction "1_1") (pintype "passive"))
      (node (ref "U5") (pin "25") (pinfunction "IO0_25") (pintype "bidirectional"))
    )
    (net (code "8") (name "/FB") (class "Default")
      (node (ref "C17") (pin "1") (pinfunction "1_1") (pintype "passive"))
      (node (ref "R12") (pin "1") (pinfunction "1_1") (pintype "passive"))
      (node (ref "R13") (pin "2") (pinfunction "2_2") (pintype "passive"))
      (node (ref "U1") (pin "7") (pinfunction "FB_7") (pintype "input"))
    )
    (net (code "9") (name "/GSM_CLK") (class "Default")
      (node (ref "R52") (pin "2") (pinfunction "2_2") (pintype "passive"))
      (node (ref "U4") (pin "16") (pinfunction "SIM_CLK_16") (pintype "passive"))
    )
    (net (code "10") (name "/GSM_DATA") (class "Default")
      (node (ref "C62") (pin "2") (pinfunction "2_2") (pintype "passive"))
      (node (ref "R51") (pin "2") (pinfunction "2_2") (pintype "passive"))
      (node (ref "U4") (pin "15") (pinfunction "SIM_DATA_15") (pintype "passive"))
    )
    (net (code "11") (name "/GSM_RST") (class "Default")
      (node (ref "R54") (pin "2") (pinfunction "2_2") (pintype "passive"))
      (node (ref "U4") (pin "17") (pinfunction "SIM_RST_17") (pintype "passive"))
    )
    (net (code "12") (name "/GSM_RX") (class "Default")
      (node (ref "R46") (pin "2") (pinfunction "2_2") (pintype "passive"))
      (node (ref "U5") (pin "28") (pinfunction "IO17_28") (pintype "bidirectional"))
    )
    (net (code "13") (name "/GSM_TX") (class "Default")
      (node (ref "R44") (pin "2") (pinfunction "2_2") (pintype "passive"))
      (node (ref "U5") (pin "27") (pinfunction "IO16_27") (pintype "bidirectional"))
    )
    (net (code "14") (name "/GSM_VCC") (class "Default")
      (node (ref "C63") (pin "2") (pinfunction "2_2") (pintype "passive"))
      (node (ref "D3") (pin "4") (pinfunction "A_4") (pintype "passive"))
      (node (ref "U4") (pin "18") (pinfunction "SIM_VDD_18") (pintype "passive"))
      (node (ref "U6") (pin "8") (pinfunction "VDD_8") (pintype "input"))
    )
    (net (code "15") (name "/LED_0") (class "Default")
      (node (ref "D5") (pin "2") (pinfunction "K_2") (pintype "passive"))
      (node (ref "U5") (pin "30") (pinfunction "IO18_30") (pintype "bidirectional"))
    )
    (net (code "16") (name "/LED_1") (class "Default")
      (node (ref "D6") (pin "2") (pinfunction "K_2") (pintype "passive"))
      (node (ref "U5") (pin "31") (pinfunction "IO19_31") (pintype "bidirectional"))
    )
    (net (code "17") (name "/LED_2") (class "Default")
      (node (ref "D7") (pin "2") (pinfunction "K_2") (pintype "passive"))
      (node (ref "U5") (pin "8") (pinfunction "IO32_8") (pintype "bidirectional"))
    )
    (net (code "18") (name "/LED_3") (class "Default")
      (node (ref "D8") (pin "2") (pinfunction "K_2") (pintype "passive"))
      (node (ref "U5") (pin "9") (pinfunction "IO33_9") (pintype "bidirectional"))
    )
    (net (code "19") (name "/LINKLED") (class "Default")
      (node (ref "J2") (pin "11") (pinfunction "11_11") (pintype "passive"))
      (node (ref "U7") (pin "25") (pinfunction "LINKLED_25") (pintype "passive"))
    )
    (net (code "20") (name "/NFC_IRQ") (class "Default")
      (node (ref "U3") (pin "25") (pinfunction "IRQ_25") (pintype "output"))
      (node (ref "U5") (pin "37") (pinfunction "IO23_37") (pintype "bidirectional"))
    )
    (net (code "21") (name "/NFC_PDN") (class "Default")
      (node (ref "U3") (pin "38") (pinfunction "RSTPDN_38") (pintype "input"))
      (node (ref "U5") (pin "26") (pinfunction "IO4_26") (pintype "bidirectional"))
    )
    (net (code "22") (name "/NFC_RST") (class "Default")
      (node (ref "U3") (pin "26") (pinfunction "RSTOUTN_26") (pintype "output"))
      (node (ref "U5") (pin "29") (pinfunction "IO5_29") (pintype "bidirectional"))
    )
    (net (code "23") (name "/PMODE0") (class "Default")
      (node (ref "R30") (pin "1") (pinfunction "1_1") (pintype "passive"))
      (node (ref "R60") (pin "2") (pinfunction "2_2") (pintype "passive"))
      (node (ref "U7") (pin "45") (pinfunction "PMODE0_45") (pintype "passive"))
    )
    (net (code "24") (name "/PMODE1") (class "Default")
      (node (ref "R33") (pin "1") (pinfunction "1_1") (pintype "passive"))
      (node (ref "R61") (pin "2") (pinfunction "2_2") (pintype "passive"))
      (node (ref "U7") (pin "44") (pinfunction "PMODE1_44") (pintype "passive"))
    )
    (net (code "25") (name "/PMODE2") (class "Default")
      (node (ref "R59") (pin "1") (pinfunction "1_1") (pintype "passive"))
      (node (ref "R62") (pin "2") (pinfunction "2_2") (pintype "passive"))
      (node (ref "U7") (pin "43") (pinfunction "PMODE2_43") (pintype "passive"))
    )
    (net (code "26") (name "/PRE") (class "Default")
      (node (ref "C1") (pin "2") (pinfunction "2_2") (pintype "passive"))
      (node (ref "C5") (pin "1") (pinfunction "1_1") (pintype "passive"))
      (node (ref "D1") (pin "4") (pinfunction "Common_cathode_4") (pintype "passive"))
      (node (ref "L1") (pin "1") (pinfunction "1_1") (pintype "passive"))
      (node (ref "U1") (pin "17") (pinfunction "SW_17") (pintype "power_in"))
      (node (ref "U1") (pin "18") (pinfunction "SW_18") (pintype "power_in"))
      (node (ref "U1") (pin "19") (pinfunction "PRE_19") (pintype "open_collector"))
    )
    (net (code "27") (name "/RCT") (class "Default")
      (node (ref "C43") (pin "1") (pinfunction "1_1") (pintype "passive"))
      (node (ref "J2") (pin "5") (pinfunction "5_5") (pintype "passive"))
      (node (ref "R40") (pin "2") (pinfunction "2_2") (pintype "passive"))
      (node (ref "R43") (pin "1") (pinfunction "1_1") (pintype "passive"))
    )
    (net (code "28") (name "/REMOTE_ON_OFF_CTL") (class "Default")
      (node (ref "Q1") (pin "1") (pinfunction "G_1") (pintype "passive"))
      (node (ref "Q2") (pin "1") (pinfunction "G_1") (pintype "passive"))
      (node (ref "U5") (pin "14") (pinfunction "IO12_14") (pintype "bidirectional"))
    )
    (net (code "29") (name "/RX") (class "Default")
      (node (ref "C42") (pin "2") (pinfunction "2_2") (pintype "passive"))
      (node (ref "R41") (pin "1") (pinfunction "1_1") (pintype "passive"))
      (node (ref "U3") (pin "10") (pinfunction "RX_10") (pintype "input"))
    )
    (net (code "30") (name "/RXN") (class "Default")
      (node (ref "C49") (pin "1") (pinfunction "1_1") (pintype "passive"))
      (node (ref "R43") (pin "2") (pinfunction "2_2") (pintype "passive"))
      (node (ref "U7") (pin "5") (pinfunction "RXN_5") (pintype "passive"))
    )
    (net (code "31") (name "/RXNNET") (class "Default")
      (node (ref "C49") (pin "2") (pinfunction "2_2") (pintype "passive"))
      (node (ref "J2") (pin "6") (pinfunction "6_6") (pintype "passive"))
    )
    (net (code "32") (name "/RXP") (class "Default")
      (node (ref "C41") (pin "1") (pinfunction "1_1") (pintype "passive"))
      (node (ref "R40") (pin "1") (pinfunction "1_1") (pintype "passive"))
      (node (ref "U7") (pin "6") (pinfunction "RXP_6") (pintype "passive"))
    )
    (net (code "33") (name "/RXPNET") (class "Default")
      (node (ref "C41") (pin "2") (pinfunction "2_2") (pintype "passive"))
      (node (ref "J2") (pin "3") (pinfunction "3_3") (pintype "passive"))
    )
    (net (code "34") (name "/SCL") (class "Default")
      (node (ref "R55") (pin "1") (pinfunction "1_1") (pintype "passive"))
      (node (ref "U3") (pin "27") (pinfunction "NSS_27") (pintype "bidirectional"))
      (node (ref "U5") (pin "36") (pinfunction "IO22_36") (pintype "bidirectional"))
    )
    (net (code "35") (name "/SD") (class "Default")
      (node (ref "R1") (pin "1") (pinfunction "1_1") (pintype "passive"))
      (node (ref "R2") (pin "1") (pinfunction "1_1") (pintype "passive"))
      (node (ref "U1") (pin "2") (pinfunction "SD_2") (pintype "passive"))
    )
    (net (code "36") (name "/SDA") (class "Default")
      (node (ref "R25") (pin "2") (pinfunction "2_2") (pintype "passive"))
      (node (ref "R56") (pin "1") (pinfunction "1_1") (pintype "passive"))
      (node (ref "U3") (pin "28") (pinfunction "MOSI_28") (pintype "bidirectional"))
      (node (ref "U5") (pin "33") (pinfunction "IO21_33") (pintype "bidirectional"))
    )
    (net (code "37") (name "/SIM_CLK") (class "Default")
      (node (ref "D3") (pin "6") (pinfunction "A_6") (pintype "passive"))
      (node (ref "R52") (pin "1") (pinfunction "1_1") (pintype "passive"))
      (node (ref "U6") (pin "6") (pinfunction "CLK_6") (pintype "input"))
    )
    (net (code "38") (name "/SIM_DATA") (class "Default")
      (node (ref "D3") (pin "1") (pinfunction "K_1") (pintype "passive"))
      (node (ref "R51") (pin "1") (pinfunction "1_1") (pintype "passive"))
      (node (ref "U6") (pin "3") (pinfunction "I/O_3") (pintype "bidirectional"))
    )
    (net (code "39") (name "/SIM_RST") (class "Default")
      (node (ref "D3") (pin "5") (pinfunction "A_5") (pintype "passive"))
      (node (ref "R54") (pin "1") (pinfunction "1_1") (pintype "passive"))
      (node (ref "U6") (pin "7") (pinfunction "RST_7") (pintype "input"))
    )
    (net (code "40") (name "/SPI-MISO") (class "Default")
      (node (ref "U3") (pin "29") (pinfunction "MISO_29") (pintype "bidirectional"))
      (node (ref "U5") (pin "23") (pinfunction "IO15_23") (pintype "bidirectional"))
      (node (ref "U7") (pin "34") (pinfunction "MISO_34") (pintype "passive"))
    )
    (net (code "41") (name "/SPI-MOSI") (class "Default")
      (node (ref "R25") (pin "1") (pinfunction "1_1") (pintype "passive"))
      (node (ref "U5") (pin "16") (pinfunction "IO13_16") (pintype "bidirectional"))
      (node (ref "U7") (pin "35") (pinfunction "MOSI_35") (pintype "passive"))
    )
    (net (code "42") (name "/SPI-SCLK") (class "Default")
      (node (ref "R53") (pin "2") (pinfunction "2_2") (pintype "passive"))
      (node (ref "U3") (pin "30") (pinfunction "SCK_30") (pintype "bidirectional"))
      (node (ref "U5") (pin "24") (pinfunction "IO2_24") (pintype "bidirectional"))
      (node (ref "U7") (pin "33") (pinfunction "SCLK_33") (pintype "passive"))
    )
    (net (code "43") (name "/TCT") (class "Default")
      (node (ref "C25") (pin "1") (pinfunction "1_1") (pintype "passive"))
      (node (ref "J2") (pin "4") (pinfunction "4_4") (pintype "passive"))
      (node (ref "R17") (pin "2") (pinfunction "2_2") (pintype "passive"))
    )
    (net (code "44") (name "/TXN") (class "Default")
      (node (ref "J2") (pin "2") (pinfunction "2_2") (pintype "passive"))
      (node (ref "R16") (pin "2") (pinfunction "2_2") (pintype "passive"))
      (node (ref "U7") (pin "1") (pinfunction "TXN_1") (pintype "passive"))
    )
    (net (code "45") (name "/TXP") (class "Default")
      (node (ref "J2") (pin "1") (pinfunction "1_1") (pintype "passive"))
      (node (ref "R15") (pin "2") (pinfunction "2_2") (pintype "passive"))
      (node (ref "U7") (pin "2") (pinfunction "TXP_2") (pintype "passive"))
    )
    (net (code "46") (name "/VCC-1V2") (class "Default")
      (node (ref "C48") (pin "2") (pinfunction "2_2") (pintype "passive"))
      (node (ref "U7") (pin "22") (pinfunction "1V2O_22") (pintype "passive"))
    )
    (net (code "47") (name "/VMID") (class "Default")
      (node (ref "C44") (pin "1") (pinfunction "1_1") (pintype "passive"))
      (node (ref "R41") (pin "2") (pinfunction "2_2") (pintype "passive"))
      (node (ref "U3") (pin "9") (pinfunction "VMID_9") (pintype "output"))
    )
    (net (code "48") (name "/XI") (class "Default")
      (node (ref "C22") (pin "1") (pinfunction "1_1") (pintype "passive"))
      (node (ref "R14") (pin "2") (pinfunction "2_2") (pintype "passive"))
      (node (ref "U7") (pin "30") (pinfunction "XI/CLKIN_30") (pintype "passive"))
      (node (ref "Y1") (pin "1") (pinfunction "XTAL_1_1") (pintype "passive"))
    )
    (net (code "49") (name "/XO") (class "Default")
      (node (ref "C21") (pin "1") (pinfunction "1_1") (pintype "passive"))
      (node (ref "R14") (pin "1") (pinfunction "1_1") (pintype "passive"))
      (node (ref "U7") (pin "31") (pinfunction "XO_31") (pintype "passive"))
      (node (ref "Y1") (pin "3") (pinfunction "XTAL_2_3") (pintype "passive"))
    )
    (net (code "50") (name "/XTAL1") (class "Default")
      (node (ref "C34") (pin "1") (pinfunction "1_1") (pintype "passive"))
      (node (ref "U3") (pin "14") (pinfunction "OSCIN_14") (pintype "passive"))
      (node (ref "Y3") (pin "1") (pinfunction "XTAL_1_1") (pintype "passive"))
    )
    (net (code "51") (name "/XTAL2") (class "Default")
      (node (ref "C35") (pin "1") (pinfunction "1_1") (pintype "passive"))
      (node (ref "U3") (pin "15") (pinfunction "OSCOUT_15") (pintype "passive"))
      (node (ref "Y3") (pin "3") (pinfunction "XTAL_2_3") (pintype "passive"))
    )
    (net (code "52") (name "/{slash}INT") (class "Default")
      (node (ref "R34") (pin "1") (pinfunction "1_1") (pintype "passive"))
      (node (ref "U5") (pin "11") (pinfunction "IO26_11") (pintype "bidirectional"))
      (node (ref "U7") (pin "36") (pinfunction "INTN_36") (pintype "passive"))
    )
    (net (code "53") (name "/{slash}RESET") (class "Default")
      (node (ref "R23") (pin "2") (pinfunction "2_2") (pintype "passive"))
      (node (ref "U5") (pin "12") (pinfunction "IO27_12") (pintype "bidirectional"))
      (node (ref "U7") (pin "37") (pinfunction "RSTN_37") (pintype "passive"))
    )
    (net (code "54") (name "/{slash}SPI-SCS") (class "Default")
      (node (ref "R36") (pin "1") (pinfunction "1_1") (pintype "passive"))
      (node (ref "U5") (pin "13") (pinfunction "IO14_13") (pintype "bidirectional"))
      (node (ref "U7") (pin "32") (pinfunction "SCSN_32") (pintype "passive"))
    )
    (net (code "55") (name "3v3_dig@2A") (class "Default")
      (node (ref "BUZ1") (pin "1") (pinfunction "+_1") (pintype "passive"))
      (node (ref "C10") (pin "2") (pinfunction "2_2") (pintype "passive"))
      (node (ref "C11") (pin "2") (pinfunction "2_2") (pintype "passive"))
      (node (ref "C12") (pin "2") (pinfunction "2_2") (pintype "passive"))
      (node (ref "C32") (pin "1") (pinfunction "1_1") (pintype "passive"))
      (node (ref "C55") (pin "2") (pinfunction "2_2") (pintype "passive"))
      (node (ref "C56") (pin "2") (pinfunction "2_2") (pintype "passive"))
      (node (ref "C8") (pin "2") (pinfunction "2_2") (pintype "passive"))
      (node (ref "C9") (pin "2") (pinfunction "2_2") (pintype "passive"))
      (node (ref "J3") (pin "2") (pinfunction "2_2") (pintype "passive"))
      (node (ref "L2") (pin "2") (pinfunction "2_2") (pintype "passive"))
      (node (ref "L3") (pin "1") (pinfunction "1_1") (pintype "passive"))
      (node (ref "R23") (pin "1") (pinfunction "1_1") (pintype "passive"))
      (node (ref "R27") (pin "1") (pinfunction "1_1") (pintype "passive"))
      (node (ref "R29") (pin "1") (pinfunction "1_1") (pintype "passive"))
      (node (ref "R30") (pin "2") (pinfunction "2_2") (pintype "passive"))
      (node (ref "R32") (pin "1") (pinfunction "1_1") (pintype "passive"))
      (node (ref "R33") (pin "2") (pinfunction "2_2") (pintype "passive"))
      (node (ref "R34") (pin "2") (pinfunction "2_2") (pintype "passive"))
      (node (ref "R36") (pin "2") (pinfunction "2_2") (pintype "passive"))
      (node (ref "R4") (pin "2") (pinfunction "2_2") (pintype "passive"))
      (node (ref "R47") (pin "2") (pinfunction "2_2") (pintype "passive"))
      (node (ref "R55") (pin "2") (pinfunction "2_2") (pintype "passive"))
      (node (ref "R56") (pin "2") (pinfunction "2_2") (pintype "passive"))
      (node (ref "R58") (pin "2") (pinfunction "2_2") (pintype "passive"))
      (node (ref "R59") (pin "2") (pinfunction "2_2") (pintype "passive"))
      (node (ref "R65") (pin "1") (pinfunction "1_1") (pintype "passive"))
      (node (ref "U3") (pin "40") (pinfunction "VBAT_40") (pintype "power_in"))
      (node (ref "U5") (pin "2") (pinfunction "3V3_2") (pintype "bidirectional"))
      (node (ref "U7") (pin "28") (pinfunction "VDD_28") (pintype "passive"))
    )
    (net (code "56") (name "4v3@3A") (class "Default")
      (node (ref "C13") (pin "2") (pinfunction "2_2") (pintype "passive"))
      (node (ref "C14") (pin "2") (pinfunction "2_2") (pintype "passive"))
      (node (ref "C15") (pin "2") (pinfunction "2_2") (pintype "passive"))
      (node (ref "C52") (pin "2") (pinfunction "2_2") (pintype "passive"))
      (node (ref "C53") (pin "2") (pinfunction "2_2") (pintype "passive"))
      (node (ref "C54") (pin "2") (pinfunction "2_2") (pintype "passive"))
      (node (ref "C6") (pin "1") (pinfunction "1_1") (pintype "passive"))
      (node (ref "C7") (pin "1") (pinfunction "1_1") (pintype "passive"))
      (node (ref "D2") (pin "1") (pinfunction "K_1") (pintype "passive"))
      (node (ref "L1") (pin "2") (pinfunction "2_2") (pintype "passive"))
      (node (ref "R12") (pin "2") (pinfunction "2_2") (pintype "passive"))
      (node (ref "R67") (pin "1") (pinfunction "1_1") (pintype "passive"))
      (node (ref "R68") (pin "1") (pinfunction "1_1") (pintype "passive"))
      (node (ref "R69") (pin "1") (pinfunction "1_1") (pintype "passive"))
      (node (ref "R70") (pin "1") (pinfunction "1_1") (pintype "passive"))
      (node (ref "U1") (pin "12") (pinfunction "OUT_12") (pintype "power_in"))
      (node (ref "U2") (pin "1") (pinfunction "VIN_1") (pintype "power_in"))
      (node (ref "U2") (pin "5") (pinfunction "EN_5") (pintype "input"))
      (node (ref "U4") (pin "34") (pinfunction "BAT_PROTECTED_34") (pintype "passive"))
      (node (ref "U4") (pin "35") (pinfunction "BAT_PROTECTED_35") (pintype "passive"))
    )
    (net (code "57") (name "DGND") (class "Default")
      (node (ref "C10") (pin "1") (pinfunction "1_1") (pintype "passive"))
      (node (ref "C11") (pin "1") (pinfunction "1_1") (pintype "passive"))
      (node (ref "C12") (pin "1") (pinfunction "1_1") (pintype "passive"))
      (node (ref "C13") (pin "1") (pinfunction "1_1") (pintype "passive"))
      (node (ref "C14") (pin "1") (pinfunction "1_1") (pintype "passive"))
      (node (ref "C15") (pin "1") (pinfunction "1_1") (pintype "passive"))
      (node (ref "C16") (pin "1") (pinfunction "1_1") (pintype "passive"))
      (node (ref "C18") (pin "2") (pinfunction "2_2") (pintype "passive"))
      (node (ref "C19") (pin "2") (pinfunction "2_2") (pintype "passive"))
      (node (ref "C2") (pin "2") (pinfunction "2_2") (pintype "passive"))
      (node (ref "C20") (pin "2") (pinfunction "2_2") (pintype "passive"))
      (node (ref "C21") (pin "2") (pinfunction "2_2") (pintype "passive"))
      (node (ref "C22") (pin "2") (pinfunction "2_2") (pintype "passive"))
      (node (ref "C25") (pin "2") (pinfunction "2_2") (pintype "passive"))
      (node (ref "C26") (pin "2") (pinfunction "2_2") (pintype "passive"))
      (node (ref "C27") (pin "2") (pinfunction "2_2") (pintype "passive"))
      (node (ref "C28") (pin "2") (pinfunction "2_2") (pintype "passive"))
      (node (ref "C29") (pin "1") (pinfunction "1_1") (pintype "passive"))
      (node (ref "C3") (pin "2") (pinfunction "2_2") (pintype "passive"))
      (node (ref "C30") (pin "1") (pinfunction "1_1") (pintype "passive"))
      (node (ref "C31") (pin "1") (pinfunction "1_1") (pintype "passive"))
      (node (ref "C32") (pin "2") (pinfunction "2_2") (pintype "passive"))
      (node (ref "C33") (pin "1") (pinfunction "1_1") (pintype "passive"))
      (node (ref "C34") (pin "2") (pinfunction "2_2") (pintype "passive"))
      (node (ref "C35") (pin "2") (pinfunction "2_2") (pintype "passive"))
      (node (ref "C38") (pin "2") (pinfunction "2_2") (pintype "passive"))
      (node (ref "C39") (pin "2") (pinfunction "2_2") (pintype "passive"))
      (node (ref "C40") (pin "2") (pinfunction "2_2") (pintype "passive"))
      (node (ref "C43") (pin "2") (pinfunction "2_2") (pintype "passive"))
      (node (ref "C44") (pin "2") (pinfunction "2_2") (pintype "passive"))
      (node (ref "C45") (pin "2") (pinfunction "2_2") (pintype "passive"))
      (node (ref "C46") (pin "2") (pinfunction "2_2") (pintype "passive"))
      (node (ref "C47") (pin "1") (pinfunction "1_1") (pintype "passive"))
      (node (ref "C48") (pin "1") (pinfunction "1_1") (pintype "passive"))
      (node (ref "C50") (pin "2") (pinfunction "2_2") (pintype "passive"))
      (node (ref "C51") (pin "2") (pinfunction "2_2") (pintype "passive"))
      (node (ref "C52") (pin "1") (pinfunction "1_1") (pintype "passive"))
      (node (ref "C53") (pin "1") (pinfunction "1_1") (pintype "passive"))
      (node (ref "C54") (pin "1") (pinfunction "1_1") (pintype "passive"))
      (node (ref "C55") (pin "1") (pinfunction "1_1") (pintype "passive"))
      (node (ref "C56") (pin "1") (pinfunction "1_1") (pintype "passive"))
      (node (ref "C57") (pin "1") (pinfunction "1_1") (pintype "passive"))
      (node (ref "C58") (pin "1") (pinfunction "1_1") (pintype "passive"))
      (node (ref "C59") (pin "1") (pinfunction "1_1") (pintype "passive"))
      (node (ref "C6") (pin "2") (pinfunction "2_2") (pintype "passive"))
      (node (ref "C60") (pin "1") (pinfunction "1_1") (pintype "passive"))
      (node (ref "C61") (pin "1") (pinfunction "1_1") (pintype "passive"))
      (node (ref "C62") (pin "1") (pinfunction "1_1") (pintype "passive"))
      (node (ref "C63") (pin "1") (pinfunction "1_1") (pintype "passive"))
      (node (ref "C7") (pin "2") (pinfunction "2_2") (pintype "passive"))
      (node (ref "C8") (pin "1") (pinfunction "1_1") (pintype "passive"))
      (node (ref "C9") (pin "1") (pinfunction "1_1") (pintype "passive"))
      (node (ref "D2") (pin "2") (pinfunction "A_2") (pintype "passive"))
      (node (ref "D3") (pin "2") (pinfunction "K_2") (pintype "passive"))
      (node (ref "J1") (pin "2") (pinfunction "2_2") (pintype "passive"))
      (node (ref "J2") (pin "MH1") (pinfunction "MH1_MH1") (pintype "passive"))
      (node (ref "J2") (pin "MH2") (pinfunction "MH2_MH2") (pintype "passive"))
      (node (ref "J3") (pin "4") (pinfunction "4_4") (pintype "passive"))
      (node (ref "Q4") (pin "2") (pinfunction "S_2") (pintype "passive"))
      (node (ref "R10") (pin "1") (pinfunction "1_1") (pintype "passive"))
      (node (ref "R11") (pin "2") (pinfunction "2_2") (pintype "passive"))
      (node (ref "R13") (pin "1") (pinfunction "1_1") (pintype "passive"))
      (node (ref "R18") (pin "1") (pinfunction "1_1") (pintype "passive"))
      (node (ref "R19") (pin "1") (pinfunction "1_1") (pintype "passive"))
      (node (ref "R2") (pin "2") (pinfunction "2_2") (pintype "passive"))
      (node (ref "R20") (pin "1") (pinfunction "1_1") (pintype "passive"))
      (node (ref "R21") (pin "1") (pinfunction "1_1") (pintype "passive"))
      (node (ref "R22") (pin "1") (pinfunction "1_1") (pintype "passive"))
      (node (ref "R26") (pin "1") (pinfunction "1_1") (pintype "passive"))
      (node (ref "R31") (pin "1") (pinfunction "1_1") (pintype "passive"))
      (node (ref "R38") (pin "1") (pinfunction "1_1") (pintype "passive"))
      (node (ref "R42") (pin "1") (pinfunction "1_1") (pintype "passive"))
      (node (ref "R45") (pin "1") (pinfunction "1_1") (pintype "passive"))
      (node (ref "R48") (pin "1") (pinfunction "1_1") (pintype "passive"))
      (node (ref "R53") (pin "1") (pinfunction "1_1") (pintype "passive"))
      (node (ref "R57") (pin "1") (pinfunction "1_1") (pintype "passive"))
      (node (ref "R60") (pin "1") (pinfunction "1_1") (pintype "passive"))
      (node (ref "R61") (pin "1") (pinfunction "1_1") (pintype "passive"))
      (node (ref "R62") (pin "1") (pinfunction "1_1") (pintype "passive"))
      (node (ref "R63") (pin "2") (pinfunction "2_2") (pintype "passive"))
      (node (ref "R64") (pin "1") (pinfunction "1_1") (pintype "passive"))
      (node (ref "R8") (pin "2") (pinfunction "2_2") (pintype "passive"))
      (node (ref "R9") (pin "2") (pinfunction "2_2") (pintype "passive"))
      (node (ref "RF_PCB1") (pin "2") (pinfunction "GND_2") (pintype "passive"))
      (node (ref "U1") (pin "10") (pinfunction "AGND_10") (pintype "power_in"))
      (node (ref "U1") (pin "13") (pinfunction "PGND_13") (pintype "power_in"))
      (node (ref "U1") (pin "14") (pinfunction "PGND_14") (pintype "power_in"))
      (node (ref "U1") (pin "21") (pinfunction "DAP_21") (pintype "power_in"))
      (node (ref "U2") (pin "3") (pinfunction "GND_3") (pintype "power_in"))
      (node (ref "U3") (pin "1") (pinfunction "DVSS_1") (pintype "power_in"))
      (node (ref "U3") (pin "11") (pinfunction "AVSS_11") (pintype "power_in"))
      (node (ref "U3") (pin "3") (pinfunction "TVSS1_3") (pintype "power_in"))
      (node (ref "U3") (pin "41") (pinfunction "EP_41") (pintype "passive"))
      (node (ref "U3") (pin "7") (pinfunction "TVSS2_7") (pintype "power_in"))
      (node (ref "U4") (pin "13") (pinfunction "GND_13") (pintype "passive"))
      (node (ref "U4") (pin "19") (pinfunction "GND_19") (pintype "passive"))
      (node (ref "U4") (pin "21") (pinfunction "GND_21") (pintype "passive"))
      (node (ref "U4") (pin "23") (pinfunction "UART2_RXD_23") (pintype "input"))
      (node (ref "U4") (pin "27") (pinfunction "GND_27") (pintype "power_in"))
      (node (ref "U4") (pin "30") (pinfunction "GND_30") (pintype "power_in"))
      (node (ref "U4") (pin "31") (pinfunction "GND_31") (pintype "power_in"))
      (node (ref "U4") (pin "33") (pinfunction "GND_33") (pintype "power_in"))
      (node (ref "U4") (pin "36") (pinfunction "GND_36") (pintype "power_in"))
      (node (ref "U4") (pin "37") (pinfunction "GND_37") (pintype "power_in"))
      (node (ref "U4") (pin "39") (pinfunction "PWRKEY_39") (pintype "passive"))
      (node (ref "U4") (pin "8") (pinfunction "GND_8") (pintype "power_in"))
      (node (ref "U5") (pin "1") (pinfunction "GND_1") (pintype "passive"))
      (node (ref "U5") (pin "15") (pinfunction "GND_15") (pintype "passive"))
      (node (ref "U5") (pin "38") (pinfunction "GND_38") (pintype "passive"))
      (node (ref "U5") (pin "39") (pinfunction "GND_PAD_39") (pintype "passive"))
      (node (ref "U6") (pin "1") (pinfunction "GND_1") (pintype "power_in"))
      (node (ref "U6") (pin "9") (pinfunction "TPAD_9") (pintype "power_in"))
      (node (ref "U7") (pin "14") (pinfunction "AGND_3_14") (pintype "passive"))
      (node (ref "U7") (pin "16") (pinfunction "AGND_4_16") (pintype "passive"))
      (node (ref "U7") (pin "19") (pinfunction "AGND_5_19") (pintype "passive"))
      (node (ref "U7") (pin "29") (pinfunction "GND_29") (pintype "passive"))
      (node (ref "U7") (pin "3") (pinfunction "AGND_1_3") (pintype "passive"))
      (node (ref "U7") (pin "48") (pinfunction "AGND_6_48") (pintype "passive"))
      (node (ref "U7") (pin "9") (pinfunction "AGND_2_9") (pintype "passive"))
    )
    (net (code "58") (name "NFC_VCC") (class "Default")
      (node (ref "C38") (pin "1") (pinfunction "1_1") (pintype "passive"))
      (node (ref "C51") (pin "1") (pinfunction "1_1") (pintype "passive"))
      (node (ref "FB1") (pin "2") (pinfunction "2_2") (pintype "passive"))
      (node (ref "FB2") (pin "2") (pinfunction "2_2") (pintype "passive"))
      (node (ref "U3") (pin "39") (pinfunction "DVDD_39") (pintype "power_in"))
    )
    (net (code "59") (name "Net-(BUZ1--)") (class "Default")
      (node (ref "BUZ1") (pin "2") (pinfunction "-_2") (pintype "passive"))
      (node (ref "Q4") (pin "3") (pinfunction "D_3") (pintype "passive"))
      (node (ref "R65") (pin "2") (pinfunction "2_2") (pintype "passive"))
    )
    (net (code "60") (name "Net-(C5-Pad2)") (class "Default")
      (node (ref "C5") (pin "2") (pinfunction "2_2") (pintype "passive"))
      (node (ref "R57") (pin "2") (pinfunction "2_2") (pintype "passive"))
    )
    (net (code "61") (name "Net-(C17-Pad2)") (class "Default")
      (node (ref "C17") (pin "2") (pinfunction "2_2") (pintype "passive"))
      (node (ref "R7") (pin "2") (pinfunction "2_2") (pintype "passive"))
    )
    (net (code "62") (name "Net-(C23-Pad1)") (class "Default")
      (node (ref "C23") (pin "1") (pinfunction "1_1") (pintype "passive"))
      (node (ref "C24") (pin "1") (pinfunction "1_1") (pintype "passive"))
      (node (ref "C26") (pin "1") (pinfunction "1_1") (pintype "passive"))
      (node (ref "C27") (pin "1") (pinfunction "1_1") (pintype "passive"))
      (node (ref "R24") (pin "1") (pinfunction "1_1") (pintype "passive"))
    )
    (net (code "63") (name "Net-(C23-Pad2)") (class "Default")
      (node (ref "C23") (pin "2") (pinfunction "2_2") (pintype "passive"))
      (node (ref "C24") (pin "2") (pinfunction "2_2") (pintype "passive"))
      (node (ref "C28") (pin "1") (pinfunction "1_1") (pintype "passive"))
      (node (ref "R28") (pin "1") (pinfunction "1_1") (pintype "passive"))
    )
    (net (code "64") (name "Net-(C29-Pad2)") (class "Default")
      (node (ref "C29") (pin "2") (pinfunction "2_2") (pintype "passive"))
      (node (ref "C36") (pin "1") (pinfunction "1_1") (pintype "passive"))
      (node (ref "C37") (pin "1") (pinfunction "1_1") (pintype "passive"))
      (node (ref "R35") (pin "1") (pinfunction "1_1") (pintype "passive"))
      (node (ref "R39") (pin "1") (pinfunction "1_1") (pintype "passive"))
    )
    (net (code "65") (name "Net-(C30-Pad2)") (class "Default")
      (node (ref "C30") (pin "2") (pinfunction "2_2") (pintype "passive"))
      (node (ref "C31") (pin "2") (pinfunction "2_2") (pintype "passive"))
      (node (ref "C36") (pin "2") (pinfunction "2_2") (pintype "passive"))
      (node (ref "C37") (pin "2") (pinfunction "2_2") (pintype "passive"))
      (node (ref "R37") (pin "2") (pinfunction "2_2") (pintype "passive"))
    )
    (net (code "66") (name "Net-(C42-Pad1)") (class "Default")
      (node (ref "C42") (pin "1") (pinfunction "1_1") (pintype "passive"))
      (node (ref "R39") (pin "2") (pinfunction "2_2") (pintype "passive"))
    )
    (net (code "67") (name "Net-(C58-Pad2)") (class "Default")
      (node (ref "C58") (pin "2") (pinfunction "2_2") (pintype "passive"))
      (node (ref "C59") (pin "2") (pinfunction "2_2") (pintype "passive"))
      (node (ref "R49") (pin "1") (pinfunction "1_1") (pintype "passive"))
      (node (ref "R50") (pin "2") (pinfunction "2_2") (pintype "passive"))
    )
    (net (code "68") (name "Net-(D1-1_Anode)") (class "Default")
      (node (ref "D1") (pin "1") (pinfunction "1_Anode_1") (pintype "passive"))
      (node (ref "D1") (pin "3") (pinfunction "2_Anode_3") (pintype "passive"))
      (node (ref "U1") (pin "15") (pinfunction "IS_15") (pintype "input"))
      (node (ref "U1") (pin "16") (pinfunction "IS_16") (pintype "input"))
    )
    (net (code "69") (name "Net-(D4-A)") (class "Default")
      (node (ref "D4") (pin "2") (pinfunction "A_2") (pintype "passive"))
      (node (ref "Q3") (pin "1") (pinfunction "G_1") (pintype "passive"))
      (node (ref "R48") (pin "2") (pinfunction "2_2") (pintype "passive"))
    )
    (net (code "70") (name "Net-(D5-A)") (class "Default")
      (node (ref "D5") (pin "1") (pinfunction "A_1") (pintype "passive"))
      (node (ref "R67") (pin "2") (pinfunction "2_2") (pintype "passive"))
    )
    (net (code "71") (name "Net-(D6-A)") (class "Default")
      (node (ref "D6") (pin "1") (pinfunction "A_1") (pintype "passive"))
      (node (ref "R68") (pin "2") (pinfunction "2_2") (pintype "passive"))
    )
    (net (code "72") (name "Net-(D7-A)") (class "Default")
      (node (ref "D7") (pin "1") (pinfunction "A_1") (pintype "passive"))
      (node (ref "R69") (pin "2") (pinfunction "2_2") (pintype "passive"))
    )
    (net (code "73") (name "Net-(D8-A)") (class "Default")
      (node (ref "D8") (pin "1") (pinfunction "A_1") (pintype "passive"))
      (node (ref "R70") (pin "2") (pinfunction "2_2") (pintype "passive"))
    )
    (net (code "74") (name "Net-(J2-Pad9)") (class "Default")
      (node (ref "J2") (pin "9") (pinfunction "9_9") (pintype "passive"))
      (node (ref "R29") (pin "2") (pinfunction "2_2") (pintype "passive"))
    )
    (net (code "75") (name "Net-(J2-Pad12)") (class "Default")
      (node (ref "J2") (pin "12") (pinfunction "12_12") (pintype "passive"))
      (node (ref "R32") (pin "2") (pinfunction "2_2") (pintype "passive"))
    )
    (net (code "76") (name "Net-(Q1-D)") (class "Default")
      (node (ref "J4") (pin "1") (pinfunction "1_1") (pintype "passive"))
      (node (ref "Q1") (pin "3") (pinfunction "D_3") (pintype "passive"))
    )
    (net (code "77") (name "Net-(Q1-S)") (class "Default")
      (node (ref "Q1") (pin "2") (pinfunction "S_2") (pintype "passive"))
      (node (ref "R3") (pin "2") (pinfunction "2_2") (pintype "passive"))
      (node (ref "R6") (pin "2") (pinfunction "2_2") (pintype "passive"))
      (node (ref "R8") (pin "1") (pinfunction "1_1") (pintype "passive"))
    )
    (net (code "78") (name "Net-(Q2-D)") (class "Default")
      (node (ref "J4") (pin "2") (pinfunction "2_2") (pintype "passive"))
      (node (ref "Q2") (pin "3") (pinfunction "D_3") (pintype "passive"))
      (node (ref "R3") (pin "1") (pinfunction "1_1") (pintype "passive"))
    )
    (net (code "79") (name "Net-(Q2-S)") (class "Default")
      (node (ref "Q2") (pin "2") (pinfunction "S_2") (pintype "passive"))
      (node (ref "R6") (pin "1") (pinfunction "1_1") (pintype "passive"))
      (node (ref "R9") (pin "1") (pinfunction "1_1") (pintype "passive"))
    )
    (net (code "80") (name "Net-(Q3-D)") (class "Default")
      (node (ref "J1") (pin "1") (pinfunction "1_1") (pintype "passive"))
      (node (ref "Q3") (pin "2") (pinfunction "D_2") (pintype "passive"))
    )
    (net (code "81") (name "Net-(Q4-G)") (class "Default")
      (node (ref "Q4") (pin "1") (pinfunction "G_1") (pintype "passive"))
      (node (ref "R66") (pin "1") (pinfunction "1_1") (pintype "passive"))
    )
    (net (code "82") (name "Net-(R11-Pad1)") (class "Default")
      (node (ref "R11") (pin "1") (pinfunction "1_1") (pintype "passive"))
      (node (ref "R5") (pin "2") (pinfunction "2_2") (pintype "passive"))
    )
    (net (code "83") (name "Net-(R24-Pad2)") (class "Default")
      (node (ref "R24") (pin "2") (pinfunction "2_2") (pintype "passive"))
      (node (ref "R63") (pin "1") (pinfunction "1_1") (pintype "passive"))
    )
    (net (code "84") (name "Net-(R37-Pad1)") (class "Default")
      (node (ref "R37") (pin "1") (pinfunction "1_1") (pintype "passive"))
      (node (ref "R64") (pin "2") (pinfunction "2_2") (pintype "passive"))
    )
    (net (code "85") (name "Net-(RF_PCB1-F)") (class "Default")
      (node (ref "C60") (pin "2") (pinfunction "2_2") (pintype "passive"))
      (node (ref "R50") (pin "1") (pinfunction "1_1") (pintype "passive"))
      (node (ref "RF_PCB1") (pin "1") (pinfunction "F_1") (pintype "passive"))
    )
    (net (code "86") (name "Net-(U1-BST)") (class "Default")
      (node (ref "C1") (pin "1") (pinfunction "1_1") (pintype "passive"))
      (node (ref "U1") (pin "20") (pinfunction "BST_20") (pintype "passive"))
    )
    (net (code "87") (name "Net-(U1-COMP)") (class "Default")
      (node (ref "R7") (pin "1") (pinfunction "1_1") (pintype "passive"))
      (node (ref "U1") (pin "6") (pinfunction "COMP_6") (pintype "passive"))
    )
    (net (code "88") (name "Net-(U1-RAMP)") (class "Default")
      (node (ref "C18") (pin "1") (pinfunction "1_1") (pintype "passive"))
      (node (ref "U1") (pin "9") (pinfunction "RAMP_9") (pintype "passive"))
    )
    (net (code "89") (name "Net-(U1-RT)") (class "Default")
      (node (ref "R5") (pin "1") (pinfunction "1_1") (pintype "passive"))
      (node (ref "U1") (pin "8") (pinfunction "RT_8") (pintype "input"))
    )
    (net (code "90") (name "Net-(U1-SS)") (class "Default")
      (node (ref "C19") (pin "1") (pinfunction "1_1") (pintype "passive"))
      (node (ref "U1") (pin "11") (pinfunction "SS_11") (pintype "input"))
    )
    (net (code "91") (name "Net-(U1-VCC)") (class "Default")
      (node (ref "C16") (pin "2") (pinfunction "2_2") (pintype "passive"))
      (node (ref "U1") (pin "1") (pinfunction "VCC_1") (pintype "power_in"))
    )
    (net (code "92") (name "Net-(U2-BST)") (class "Default")
      (node (ref "C4") (pin "2") (pinfunction "2_2") (pintype "passive"))
      (node (ref "U2") (pin "4") (pinfunction "BST_4") (pintype "output"))
    )
    (net (code "93") (name "Net-(U2-FB)") (class "Default")
      (node (ref "R10") (pin "2") (pinfunction "2_2") (pintype "passive"))
      (node (ref "R4") (pin "1") (pinfunction "1_1") (pintype "passive"))
      (node (ref "U2") (pin "6") (pinfunction "FB_6") (pintype "input"))
    )
    (net (code "94") (name "Net-(U2-SW)") (class "Default")
      (node (ref "C4") (pin "1") (pinfunction "1_1") (pintype "passive"))
      (node (ref "L2") (pin "1") (pinfunction "1_1") (pintype "passive"))
      (node (ref "U2") (pin "2") (pinfunction "SW_2") (pintype "output"))
    )
    (net (code "95") (name "Net-(U3-I0)") (class "Default")
      (node (ref "R26") (pin "2") (pinfunction "2_2") (pintype "passive"))
      (node (ref "U3") (pin "16") (pinfunction "I0_16") (pintype "bidirectional"))
    )
    (net (code "96") (name "Net-(U3-I1)") (class "Default")
      (node (ref "R27") (pin "2") (pinfunction "2_2") (pintype "passive"))
      (node (ref "U3") (pin "17") (pinfunction "I1_17") (pintype "bidirectional"))
    )
    (net (code "97") (name "Net-(U3-PVDD)") (class "Default")
      (node (ref "C40") (pin "1") (pinfunction "1_1") (pintype "passive"))
      (node (ref "U3") (pin "23") (pinfunction "PVDD_23") (pintype "power_in"))
    )
    (net (code "98") (name "Net-(U3-SVDD)") (class "Default")
      (node (ref "C39") (pin "1") (pinfunction "1_1") (pintype "passive"))
      (node (ref "U3") (pin "37") (pinfunction "SVDD_37") (pintype "power_in"))
    )
    (net (code "99") (name "Net-(U3-TESTEN)") (class "Default")
      (node (ref "R31") (pin "2") (pinfunction "2_2") (pintype "passive"))
      (node (ref "U3") (pin "18") (pinfunction "TESTEN_18") (pintype "input"))
    )
    (net (code "100") (name "Net-(U3-TVDD)") (class "Default")
      (node (ref "C50") (pin "1") (pinfunction "1_1") (pintype "passive"))
      (node (ref "FB1") (pin "1") (pinfunction "1_1") (pintype "passive"))
      (node (ref "U3") (pin "5") (pinfunction "TVDD_5") (pintype "power_in"))
    )
    (net (code "101") (name "Net-(U3-TX1)") (class "Default")
      (node (ref "R28") (pin "2") (pinfunction "2_2") (pintype "passive"))
      (node (ref "U3") (pin "4") (pinfunction "TX1_4") (pintype "output"))
    )
    (net (code "102") (name "Net-(U3-TX2)") (class "Default")
      (node (ref "R35") (pin "2") (pinfunction "2_2") (pintype "passive"))
      (node (ref "U3") (pin "6") (pinfunction "TX2_6") (pintype "output"))
    )
    (net (code "103") (name "Net-(U4-GSM_ANT)") (class "Default")
      (node (ref "C57") (pin "2") (pinfunction "2_2") (pintype "passive"))
      (node (ref "R49") (pin "2") (pinfunction "2_2") (pintype "passive"))
      (node (ref "U4") (pin "32") (pinfunction "GSM_ANT_32") (pintype "passive"))
    )
    (net (code "104") (name "Net-(U4-UART1_RXD)") (class "Default")
      (node (ref "R45") (pin "2") (pinfunction "2_2") (pintype "passive"))
      (node (ref "R46") (pin "1") (pinfunction "1_1") (pintype "passive"))
      (node (ref "U4") (pin "2") (pinfunction "UART1_RXD_2") (pintype "input"))
    )
    (net (code "105") (name "Net-(U4-UART1_TXD)") (class "Default")
      (node (ref "R44") (pin "1") (pinfunction "1_1") (pintype "passive"))
      (node (ref "U4") (pin "1") (pinfunction "UART1_TXD_1") (pintype "output"))
    )
    (net (code "106") (name "Net-(U7-EXRES1)") (class "Default")
      (node (ref "R38") (pin "2") (pinfunction "2_2") (pintype "passive"))
      (node (ref "U7") (pin "10") (pinfunction "EXRES1_10") (pintype "passive"))
    )
    (net (code "107") (name "Net-(U7-RSVD_1)") (class "Default")
      (node (ref "R42") (pin "2") (pinfunction "2_2") (pintype "passive"))
      (node (ref "U7") (pin "23") (pinfunction "RSVD_1_23") (pintype "passive"))
    )
    (net (code "108") (name "Net-(U7-RSVD_2)") (class "Default")
      (node (ref "R22") (pin "2") (pinfunction "2_2") (pintype "passive"))
      (node (ref "U7") (pin "38") (pinfunction "RSVD_2_38") (pintype "passive"))
    )
    (net (code "109") (name "Net-(U7-RSVD_3)") (class "Default")
      (node (ref "R21") (pin "2") (pinfunction "2_2") (pintype "passive"))
      (node (ref "U7") (pin "39") (pinfunction "RSVD_3_39") (pintype "passive"))
    )
    (net (code "110") (name "Net-(U7-RSVD_4)") (class "Default")
      (node (ref "R20") (pin "2") (pinfunction "2_2") (pintype "passive"))
      (node (ref "U7") (pin "40") (pinfunction "RSVD_4_40") (pintype "passive"))
    )
    (net (code "111") (name "Net-(U7-RSVD_5)") (class "Default")
      (node (ref "R19") (pin "2") (pinfunction "2_2") (pintype "passive"))
      (node (ref "U7") (pin "41") (pinfunction "RSVD_5_41") (pintype "passive"))
    )
    (net (code "112") (name "Net-(U7-RSVD_6)") (class "Default")
      (node (ref "R18") (pin "2") (pinfunction "2_2") (pintype "passive"))
      (node (ref "U7") (pin "42") (pinfunction "RSVD_6_42") (pintype "passive"))
    )
    (net (code "113") (name "Net-(U7-TOCAP)") (class "Default")
      (node (ref "C47") (pin "2") (pinfunction "2_2") (pintype "passive"))
      (node (ref "U7") (pin "20") (pinfunction "TOCAP_20") (pintype "passive"))
    )
    (net (code "114") (name "VCC-3V3A") (class "Default")
      (node (ref "C20") (pin "1") (pinfunction "1_1") (pintype "passive"))
      (node (ref "C33") (pin "2") (pinfunction "2_2") (pintype "passive"))
      (node (ref "L3") (pin "2") (pinfunction "2_2") (pintype "passive"))
      (node (ref "R15") (pin "1") (pinfunction "1_1") (pintype "passive"))
      (node (ref "R16") (pin "1") (pinfunction "1_1") (pintype "passive"))
      (node (ref "R17") (pin "1") (pinfunction "1_1") (pintype "passive"))
      (node (ref "U7") (pin "11") (pinfunction "AVDD_3_11") (pintype "passive"))
      (node (ref "U7") (pin "15") (pinfunction "AVDD_4_15") (pintype "passive"))
      (node (ref "U7") (pin "17") (pinfunction "AVDD_5_17") (pintype "passive"))
      (node (ref "U7") (pin "21") (pinfunction "AVDD_6_21") (pintype "passive"))
      (node (ref "U7") (pin "4") (pinfunction "AVDD_1_4") (pintype "passive"))
      (node (ref "U7") (pin "8") (pinfunction "AVDD_2_8") (pintype "passive"))
    )
    (net (code "115") (name "V_IN") (class "Default")
      (node (ref "C2") (pin "1") (pinfunction "1_1") (pintype "passive"))
      (node (ref "C3") (pin "1") (pinfunction "1_1") (pintype "passive"))
      (node (ref "D4") (pin "1") (pinfunction "K_1") (pintype "passive"))
      (node (ref "Q3") (pin "3") (pinfunction "S_3") (pintype "passive"))
      (node (ref "R1") (pin "2") (pinfunction "2_2") (pintype "passive"))
      (node (ref "U1") (pin "3") (pinfunction "VIN_3") (pintype "power_in"))
      (node (ref "U1") (pin "4") (pinfunction "VIN_4") (pintype "power_in"))
    )
    (net (code "116") (name "unconnected-(D3-K-Pad3)") (class "Default")
      (node (ref "D3") (pin "3") (pinfunction "K_3") (pintype "passive"))
    )
    (net (code "117") (name "unconnected-(J2-Pad7)") (class "Default")
      (node (ref "J2") (pin "7") (pinfunction "7_7") (pintype "passive"))
    )
    (net (code "118") (name "unconnected-(J2-Pad8)") (class "Default")
      (node (ref "J2") (pin "8") (pinfunction "8_8") (pintype "passive"))
    )
    (net (code "119") (name "unconnected-(U1-SYNC-Pad5)") (class "Default")
      (node (ref "U1") (pin "5") (pinfunction "SYNC_5") (pintype "passive+no_connect"))
    )
    (net (code "120") (name "unconnected-(U3-AUX1-Pad12)") (class "Default")
      (node (ref "U3") (pin "12") (pinfunction "AUX1_12") (pintype "output+no_connect"))
    )
    (net (code "121") (name "unconnected-(U3-AUX2-Pad13)") (class "Default")
      (node (ref "U3") (pin "13") (pinfunction "AUX2_13") (pintype "output+no_connect"))
    )
    (net (code "122") (name "unconnected-(U3-LOADMOD-Pad2)") (class "Default")
      (node (ref "U3") (pin "2") (pinfunction "LOADMOD_2") (pintype "output+no_connect"))
    )
    (net (code "123") (name "unconnected-(U3-NC-Pad20)") (class "Default")
      (node (ref "U3") (pin "20") (pinfunction "NC_20") (pintype "passive"))
    )
    (net (code "124") (name "unconnected-(U3-NC-Pad21)") (class "Default")
      (node (ref "U3") (pin "21") (pinfunction "NC_21") (pintype "passive"))
    )
    (net (code "125") (name "unconnected-(U3-NC-Pad22)") (class "Default")
      (node (ref "U3") (pin "22") (pinfunction "NC_22") (pintype "passive"))
    )
    (net (code "126") (name "unconnected-(U3-P30-Pad24)") (class "Default")
      (node (ref "U3") (pin "24") (pinfunction "P30_24") (pintype "bidirectional+no_connect"))
    )
    (net (code "127") (name "unconnected-(U3-P31-Pad31)") (class "Default")
      (node (ref "U3") (pin "31") (pinfunction "P31_31") (pintype "bidirectional+no_connect"))
    )
    (net (code "128") (name "unconnected-(U3-P32_INT0-Pad32)") (class "Default")
      (node (ref "U3") (pin "32") (pinfunction "P32_INT0_32") (pintype "bidirectional+no_connect"))
    )
    (net (code "129") (name "unconnected-(U3-P33_INT1-Pad33)") (class "Default")
      (node (ref "U3") (pin "33") (pinfunction "P33_INT1_33") (pintype "bidirectional+no_connect"))
    )
    (net (code "130") (name "unconnected-(U3-P34-Pad34)") (class "Default")
      (node (ref "U3") (pin "34") (pinfunction "P34_34") (pintype "bidirectional+no_connect"))
    )
    (net (code "131") (name "unconnected-(U3-P35-Pad19)") (class "Default")
      (node (ref "U3") (pin "19") (pinfunction "P35_19") (pintype "bidirectional+no_connect"))
    )
    (net (code "132") (name "unconnected-(U3-SIGIN-Pad36)") (class "Default")
      (node (ref "U3") (pin "36") (pinfunction "SIGIN_36") (pintype "input+no_connect"))
    )
    (net (code "133") (name "unconnected-(U3-SIGOUT-Pad35)") (class "Default")
      (node (ref "U3") (pin "35") (pinfunction "SIGOUT_35") (pintype "output"))
    )
    (net (code "134") (name "unconnected-(U4-ADC-Pad38)") (class "Default")
      (node (ref "U4") (pin "38") (pinfunction "ADC_38") (pintype "passive"))
    )
    (net (code "135") (name "unconnected-(U4-BT_ANT-Pad20)") (class "Default")
      (node (ref "U4") (pin "20") (pinfunction "BT_ANT_20") (pintype "passive"))
    )
    (net (code "136") (name "unconnected-(U4-MICN-Pad10)") (class "Default")
      (node (ref "U4") (pin "10") (pinfunction "MICN_10") (pintype "passive"))
    )
    (net (code "137") (name "unconnected-(U4-MICP-Pad9)") (class "Default")
      (node (ref "U4") (pin "9") (pinfunction "MICP_9") (pintype "passive"))
    )
    (net (code "138") (name "unconnected-(U4-NETLIGHT-Pad41)") (class "Default")
      (node (ref "U4") (pin "41") (pinfunction "NETLIGHT_41") (pintype "passive"))
    )
    (net (code "139") (name "unconnected-(U4-RF_SYNC-Pad29)") (class "Default")
      (node (ref "U4") (pin "29") (pinfunction "RF_SYNC_29") (pintype "passive"))
    )
    (net (code "140") (name "unconnected-(U4-SIM_DET-Pad14)") (class "Default")
      (node (ref "U4") (pin "14") (pinfunction "SIM_DET_14") (pintype "passive"))
    )
    (net (code "141") (name "unconnected-(U4-SPKN-Pad12)") (class "Default")
      (node (ref "U4") (pin "12") (pinfunction "SPKN_12") (pintype "passive"))
    )
    (net (code "142") (name "unconnected-(U4-SPKP-Pad11)") (class "Default")
      (node (ref "U4") (pin "11") (pinfunction "SPKP_11") (pintype "passive"))
    )
    (net (code "143") (name "unconnected-(U4-STATUS-Pad42)") (class "Default")
      (node (ref "U4") (pin "42") (pinfunction "STATUS_42") (pintype "passive"))
    )
    (net (code "144") (name "unconnected-(U4-UART1_CTS-Pad4)") (class "Default")
      (node (ref "U4") (pin "4") (pinfunction "UART1_CTS_4") (pintype "input+no_connect"))
    )
    (net (code "145") (name "unconnected-(U4-UART1_DCD-Pad5)") (class "Default")
      (node (ref "U4") (pin "5") (pinfunction "UART1_DCD_5") (pintype "output"))
    )
    (net (code "146") (name "unconnected-(U4-UART1_DTR-Pad6)") (class "Default")
      (node (ref "U4") (pin "6") (pinfunction "UART1_DTR_6") (pintype "input+no_connect"))
    )
    (net (code "147") (name "unconnected-(U4-UART1_RI-Pad7)") (class "Default")
      (node (ref "U4") (pin "7") (pinfunction "UART1_RI_7") (pintype "output"))
    )
    (net (code "148") (name "unconnected-(U4-UART1_RTS-Pad3)") (class "Default")
      (node (ref "U4") (pin "3") (pinfunction "UART1_RTS_3") (pintype "output"))
    )
    (net (code "149") (name "unconnected-(U4-UART2_TXD-Pad22)") (class "Default")
      (node (ref "U4") (pin "22") (pinfunction "UART2_TXD_22") (pintype "output"))
    )
    (net (code "150") (name "unconnected-(U4-USB_DN-Pad26)") (class "Default")
      (node (ref "U4") (pin "26") (pinfunction "USB_DN_26") (pintype "passive"))
    )
    (net (code "151") (name "unconnected-(U4-USB_DP-Pad25)") (class "Default")
      (node (ref "U4") (pin "25") (pinfunction "USB_DP_25") (pintype "passive"))
    )
    (net (code "152") (name "unconnected-(U4-USB_VBUS-Pad24)") (class "Default")
      (node (ref "U4") (pin "24") (pinfunction "USB_VBUS_24") (pintype "passive"))
    )
    (net (code "153") (name "unconnected-(U4-VDD_EXT-Pad40)") (class "Default")
      (node (ref "U4") (pin "40") (pinfunction "VDD_EXT_40") (pintype "passive"))
    )
    (net (code "154") (name "unconnected-(U4-VRTC-Pad28)") (class "Default")
      (node (ref "U4") (pin "28") (pinfunction "VRTC_28") (pintype "passive"))
    )
    (net (code "155") (name "unconnected-(U5-CLK-Pad20)") (class "Default")
      (node (ref "U5") (pin "20") (pinfunction "CLK_20") (pintype "bidirectional"))
    )
    (net (code "156") (name "unconnected-(U5-CMD-Pad19)") (class "Default")
      (node (ref "U5") (pin "19") (pinfunction "CMD_19") (pintype "bidirectional"))
    )
    (net (code "157") (name "unconnected-(U5-IO34-Pad6)") (class "Default")
      (node (ref "U5") (pin "6") (pinfunction "IO34_6") (pintype "bidirectional"))
    )
    (net (code "158") (name "unconnected-(U5-IO35-Pad7)") (class "Default")
      (node (ref "U5") (pin "7") (pinfunction "IO35_7") (pintype "bidirectional"))
    )
    (net (code "159") (name "unconnected-(U5-NC-Pad32)") (class "Default")
      (node (ref "U5") (pin "32") (pinfunction "NC_32") (pintype "bidirectional"))
    )
    (net (code "160") (name "unconnected-(U5-SD0-Pad21)") (class "Default")
      (node (ref "U5") (pin "21") (pinfunction "SD0_21") (pintype "bidirectional"))
    )
    (net (code "161") (name "unconnected-(U5-SD1-Pad22)") (class "Default")
      (node (ref "U5") (pin "22") (pinfunction "SD1_22") (pintype "bidirectional"))
    )
    (net (code "162") (name "unconnected-(U5-SD2-Pad17)") (class "Default")
      (node (ref "U5") (pin "17") (pinfunction "SD2_17") (pintype "bidirectional"))
    )
    (net (code "163") (name "unconnected-(U5-SD3-Pad18)") (class "Default")
      (node (ref "U5") (pin "18") (pinfunction "SD3_18") (pintype "bidirectional"))
    )
    (net (code "164") (name "unconnected-(U5-SENSOR_VN-Pad5)") (class "Default")
      (node (ref "U5") (pin "5") (pinfunction "SENSOR_VN_5") (pintype "bidirectional"))
    )
    (net (code "165") (name "unconnected-(U5-SENSOR_VP-Pad4)") (class "Default")
      (node (ref "U5") (pin "4") (pinfunction "SENSOR_VP_4") (pintype "bidirectional"))
    )
    (net (code "166") (name "unconnected-(U7-DNC-Pad7)") (class "Default")
      (node (ref "U7") (pin "7") (pinfunction "DNC_7") (pintype "passive"))
    )
    (net (code "167") (name "unconnected-(U7-DUPLED-Pad26)") (class "Default")
      (node (ref "U7") (pin "26") (pinfunction "DUPLED_26") (pintype "passive"))
    )
    (net (code "168") (name "unconnected-(U7-NC_1-Pad12)") (class "Default")
      (node (ref "U7") (pin "12") (pinfunction "NC_1_12") (pintype "passive"))
    )
    (net (code "169") (name "unconnected-(U7-NC_2-Pad13)") (class "Default")
      (node (ref "U7") (pin "13") (pinfunction "NC_2_13") (pintype "passive"))
    )
    (net (code "170") (name "unconnected-(U7-NC_3-Pad46)") (class "Default")
      (node (ref "U7") (pin "46") (pinfunction "NC_3_46") (pintype "passive"))
    )
    (net (code "171") (name "unconnected-(U7-NC_4-Pad47)") (class "Default")
      (node (ref "U7") (pin "47") (pinfunction "NC_4_47") (pintype "passive"))
    )
    (net (code "172") (name "unconnected-(U7-SPDLED-Pad24)") (class "Default")
      (node (ref "U7") (pin "24") (pinfunction "SPDLED_24") (pintype "passive"))
    )
    (net (code "173") (name "unconnected-(U7-VBG-Pad18)") (class "Default")
      (node (ref "U7") (pin "18") (pinfunction "VBG_18") (pintype "passive"))
    )
    (net (code "174") (name "unconnected-(Y1-NC_1-Pad2)") (class "Default")
      (node (ref "Y1") (pin "2") (pinfunction "NC_1_2") (pintype "passive"))
    )
    (net (code "175") (name "unconnected-(Y1-NC_2-Pad4)") (class "Default")
      (node (ref "Y1") (pin "4") (pinfunction "NC_2_4") (pintype "passive"))
    )
    (net (code "176") (name "unconnected-(Y3-NC_1-Pad2)") (class "Default")
      (node (ref "Y3") (pin "2") (pinfunction "NC_1_2") (pintype "passive"))
    )
    (net (code "177") (name "unconnected-(Y3-NC_2-Pad4)") (class "Default")
      (node (ref "Y3") (pin "4") (pinfunction "NC_2_4") (pintype "passive"))
    )
  )
)
